# Relay-Board_Rack-PDU_2_1.net
KiCad netlist of a schematic drawn in EAGLE
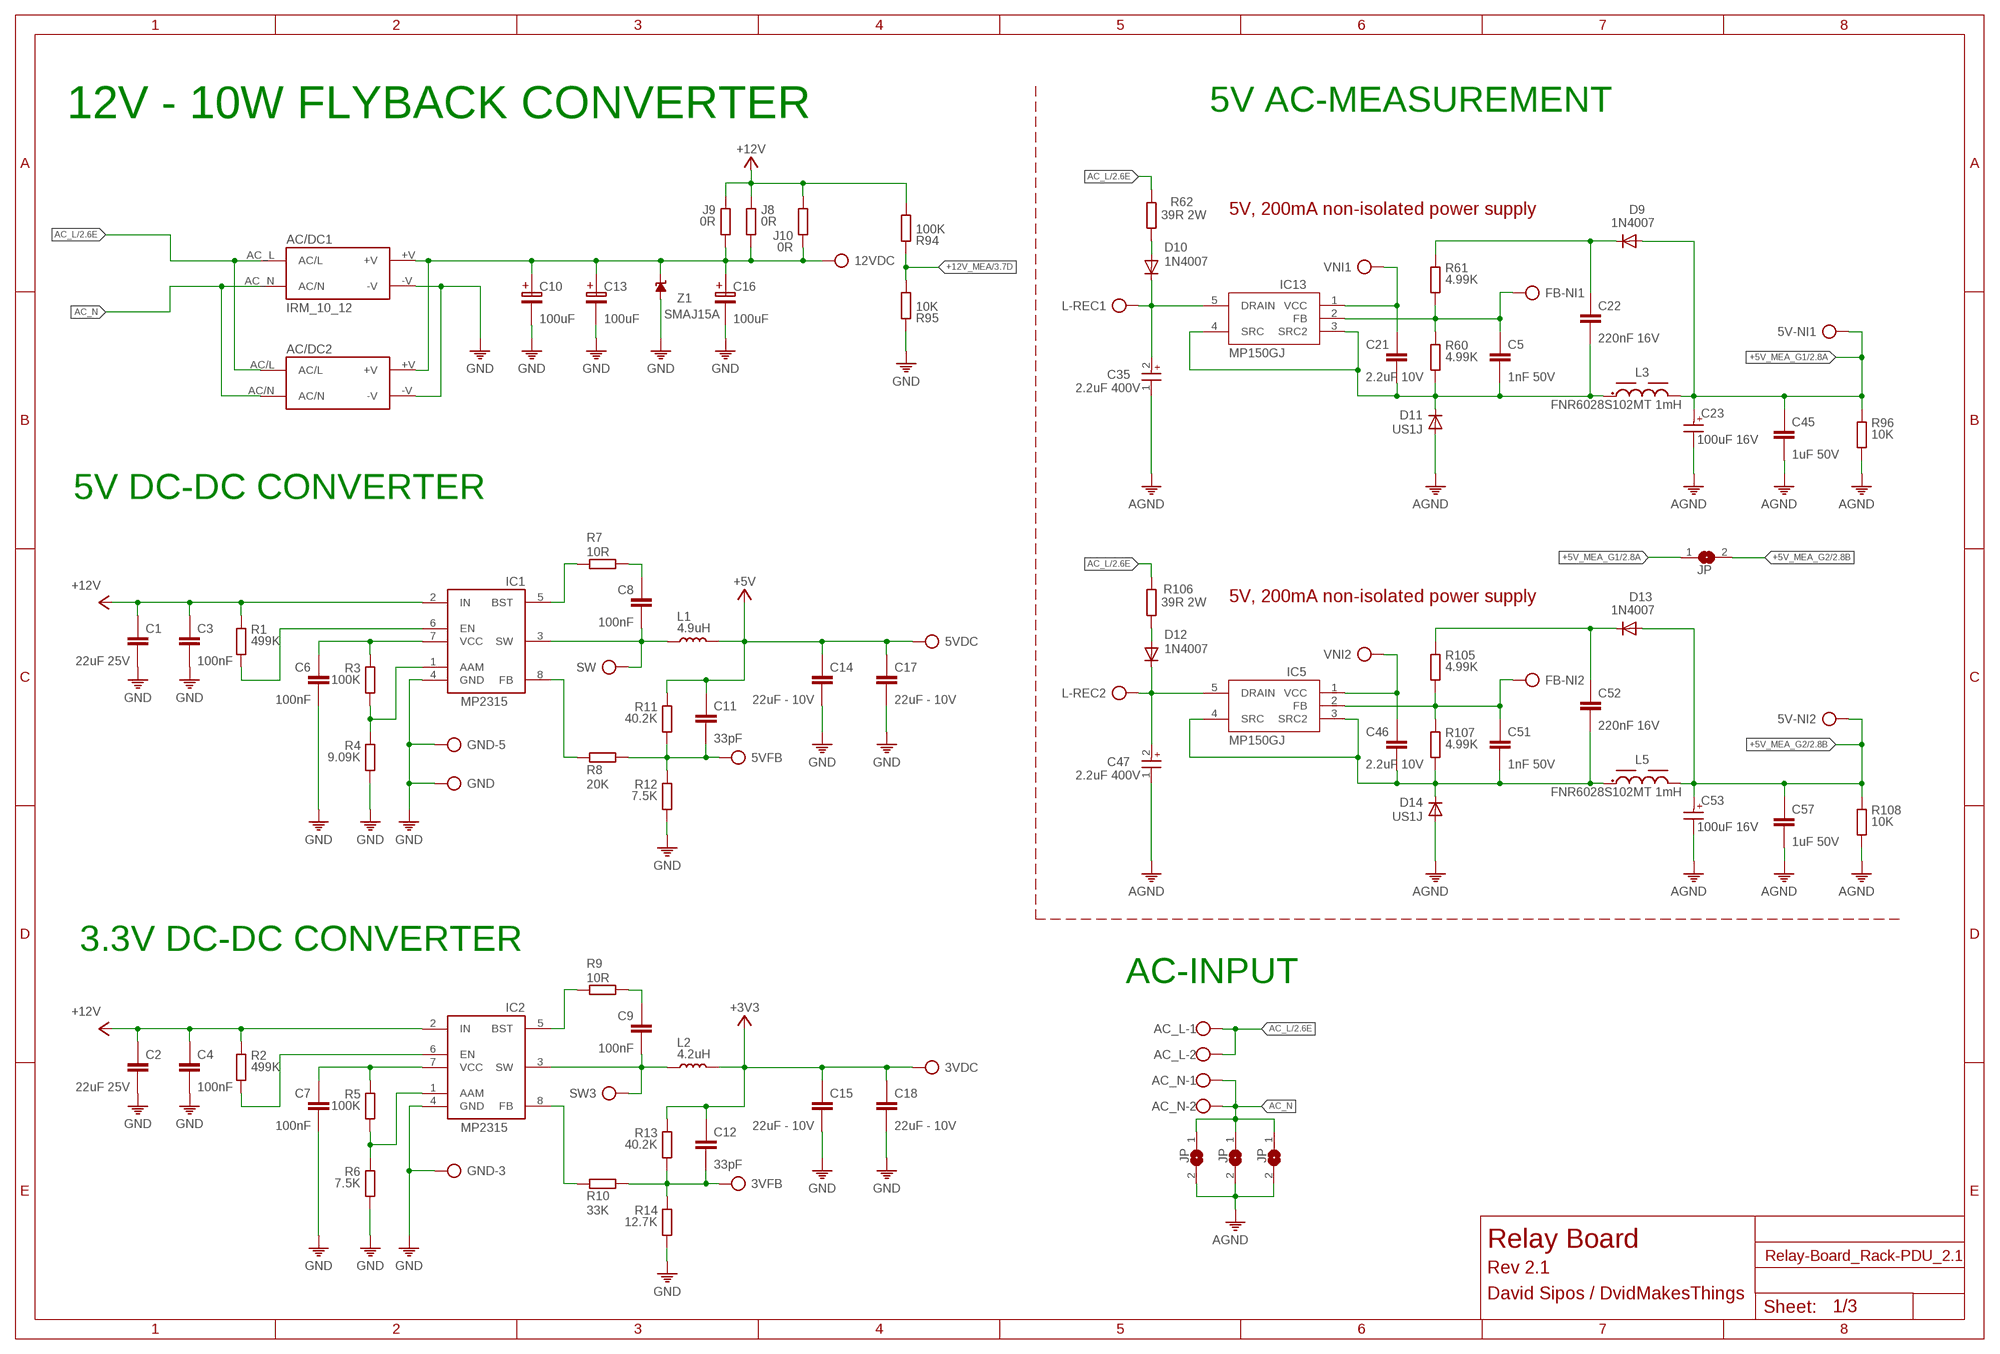
[diagram p0: schematic, sheet 1]
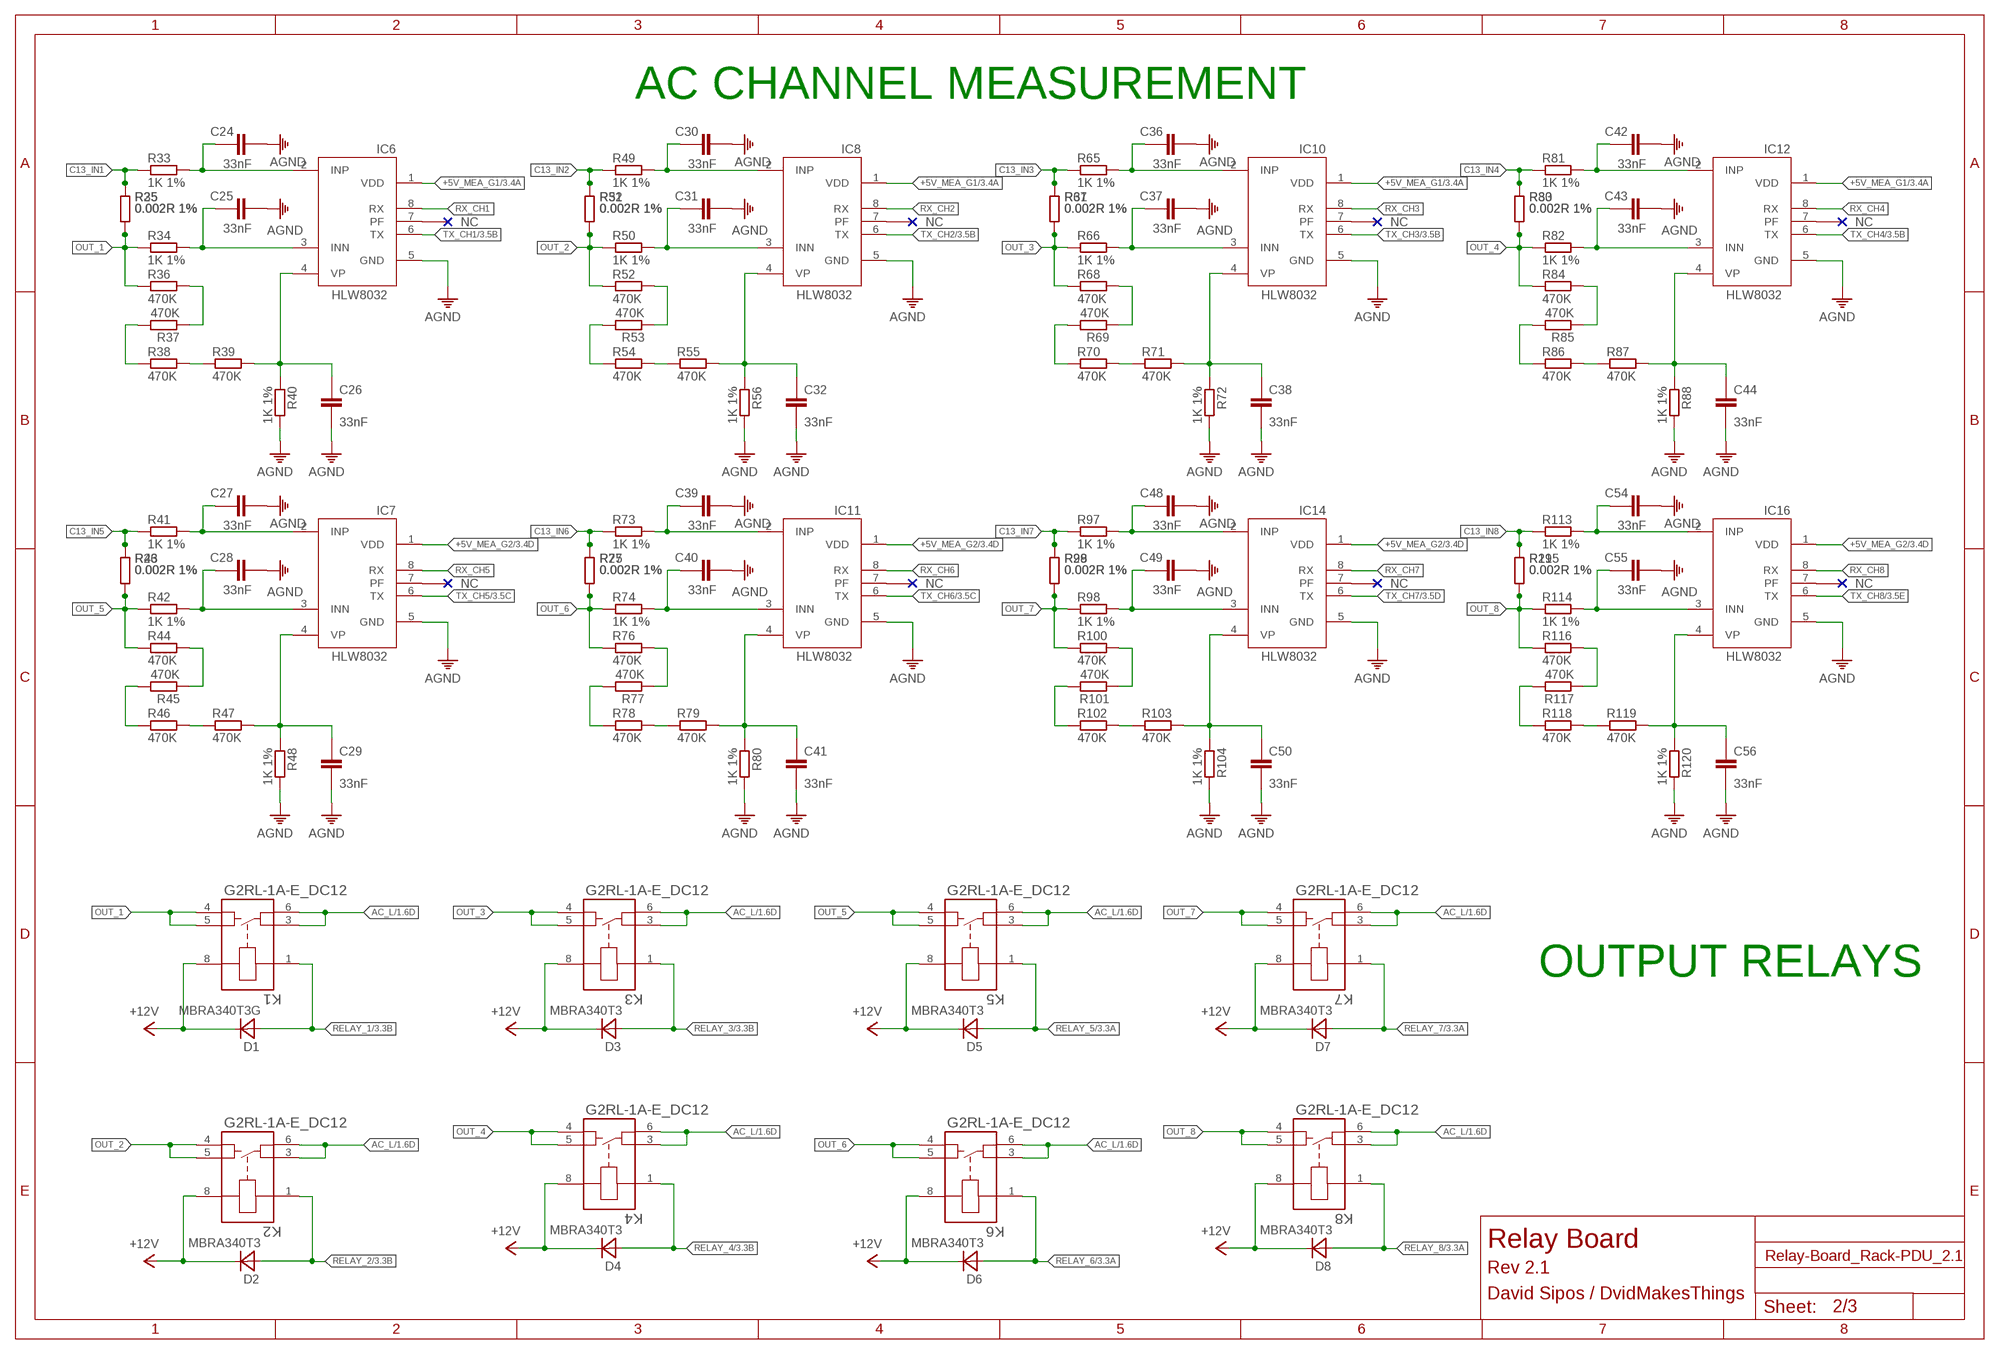
[diagram p1: schematic, sheet 2]
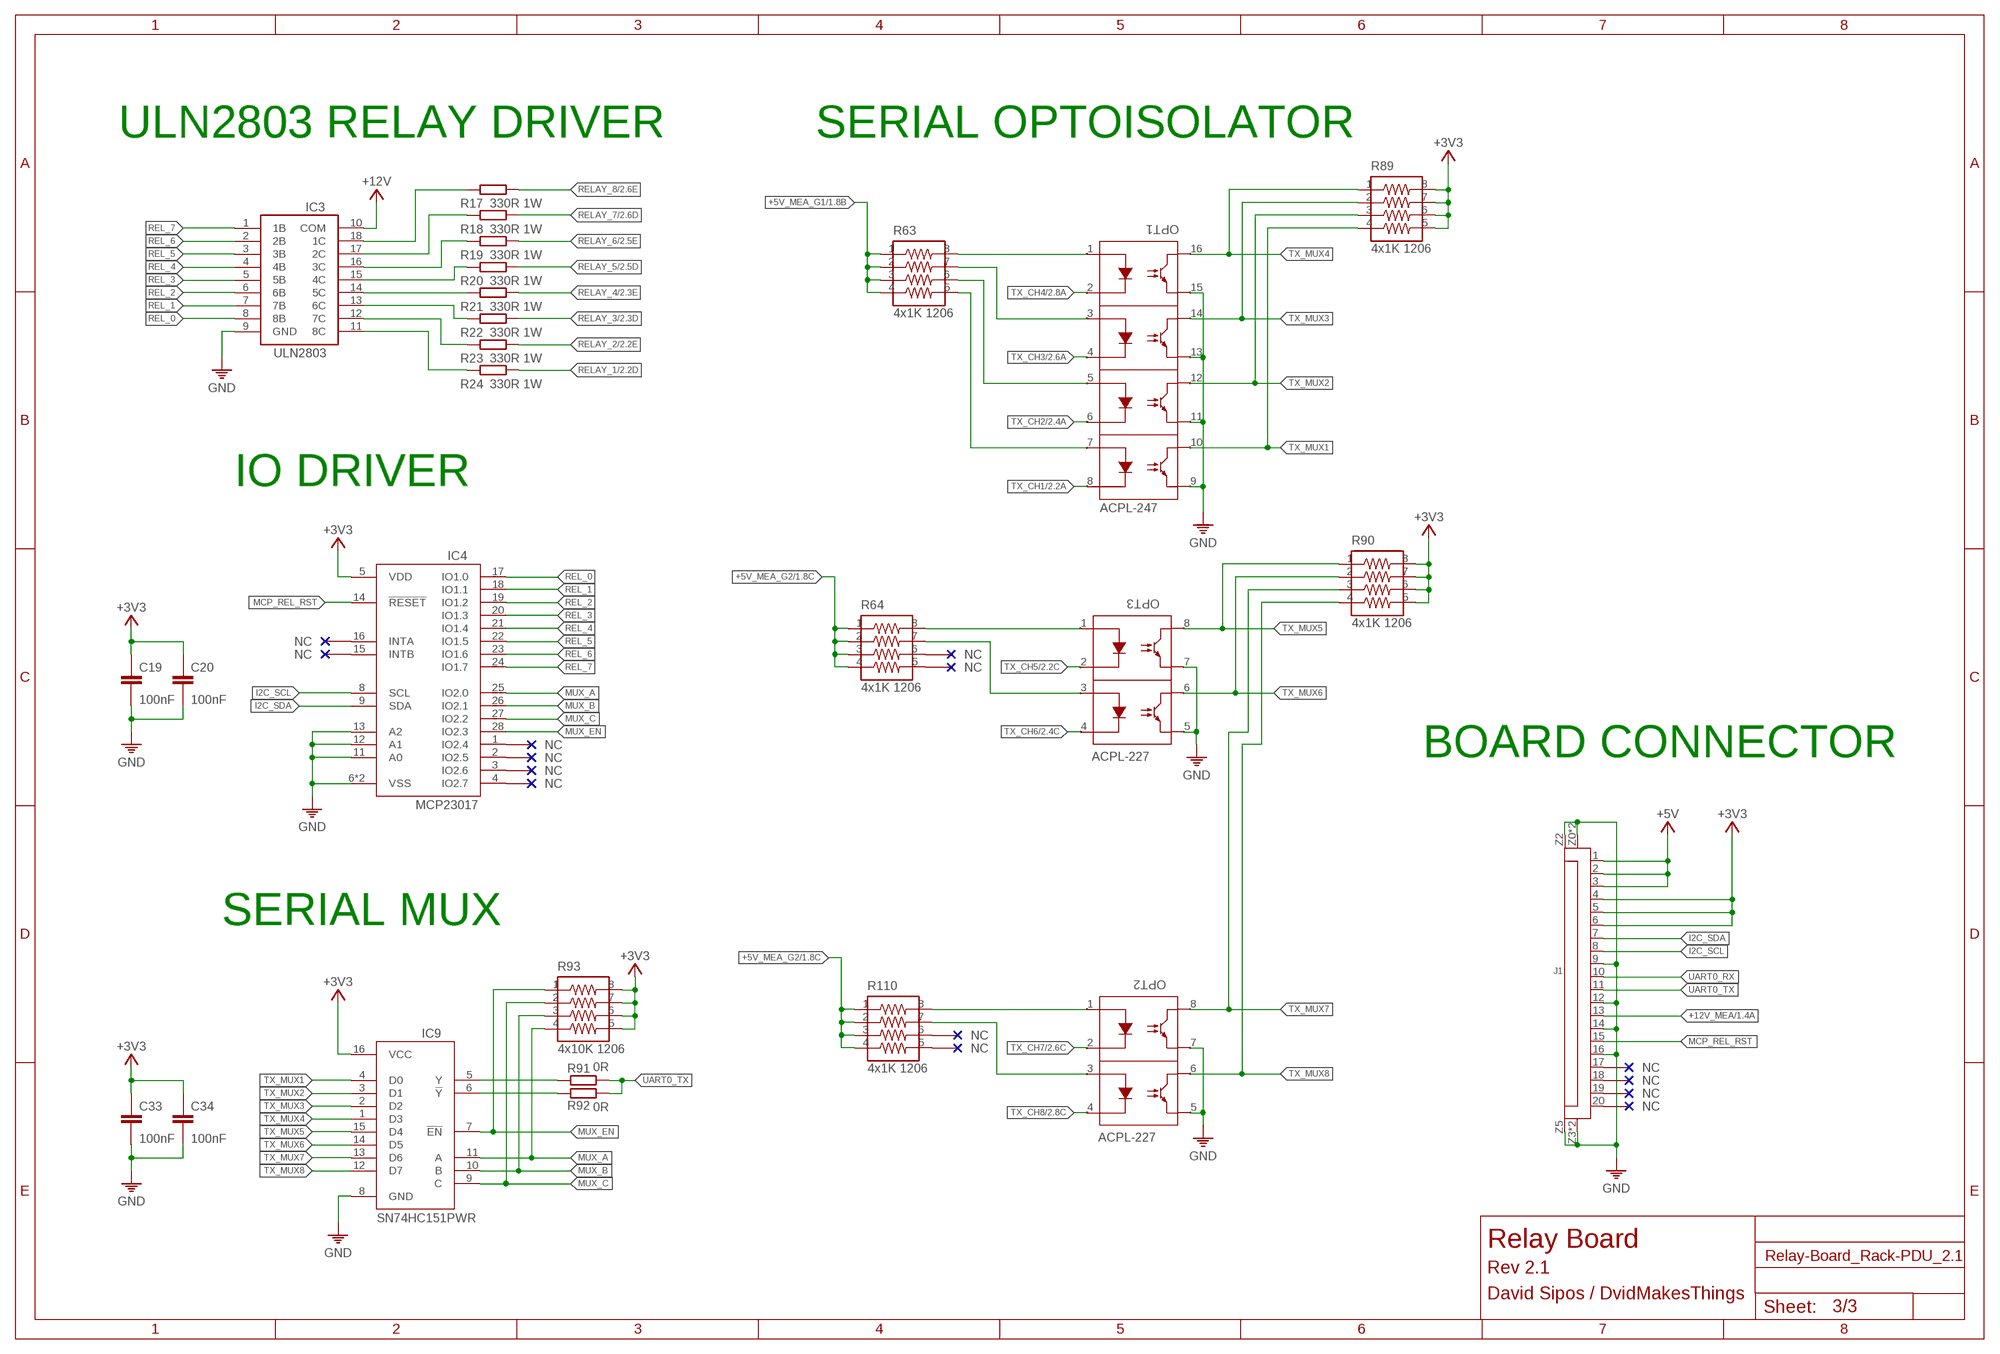
[diagram p2: schematic, sheet 3]

(export (version "E")
  (design (tool "Eeschema 10.0.6"))
  (components
    (comp (ref "C24")
      (value "33nF")
      (footprint "eagle-import:C1206")
      (libsource (lib "eagle-import") (part "C-1206"))
    )
    (comp (ref "C25")
      (value "33nF")
      (footprint "eagle-import:C1206")
      (libsource (lib "eagle-import") (part "C-1206"))
    )
    (comp (ref "C26")
      (value "33nF")
      (footprint "eagle-import:C1206")
      (libsource (lib "eagle-import") (part "C-1206"))
    )
    (comp (ref "C27")
      (value "33nF")
      (footprint "eagle-import:C1206")
      (libsource (lib "eagle-import") (part "C-1206"))
    )
    (comp (ref "C28")
      (value "33nF")
      (footprint "eagle-import:C1206")
      (libsource (lib "eagle-import") (part "C-1206"))
    )
    (comp (ref "C29")
      (value "33nF")
      (footprint "eagle-import:C1206")
      (libsource (lib "eagle-import") (part "C-1206"))
    )
    (comp (ref "C30")
      (value "33nF")
      (footprint "eagle-import:C1206")
      (libsource (lib "eagle-import") (part "C-1206"))
    )
    (comp (ref "C31")
      (value "33nF")
      (footprint "eagle-import:C1206")
      (libsource (lib "eagle-import") (part "C-1206"))
    )
    (comp (ref "C32")
      (value "33nF")
      (footprint "eagle-import:C1206")
      (libsource (lib "eagle-import") (part "C-1206"))
    )
    (comp (ref "C36")
      (value "33nF")
      (footprint "eagle-import:C1206")
      (libsource (lib "eagle-import") (part "C-1206"))
    )
    (comp (ref "C37")
      (value "33nF")
      (footprint "eagle-import:C1206")
      (libsource (lib "eagle-import") (part "C-1206"))
    )
    (comp (ref "C38")
      (value "33nF")
      (footprint "eagle-import:C1206")
      (libsource (lib "eagle-import") (part "C-1206"))
    )
    (comp (ref "C39")
      (value "33nF")
      (footprint "eagle-import:C1206")
      (libsource (lib "eagle-import") (part "C-1206"))
    )
    (comp (ref "C40")
      (value "33nF")
      (footprint "eagle-import:C1206")
      (libsource (lib "eagle-import") (part "C-1206"))
    )
    (comp (ref "C41")
      (value "33nF")
      (footprint "eagle-import:C1206")
      (libsource (lib "eagle-import") (part "C-1206"))
    )
    (comp (ref "C42")
      (value "33nF")
      (footprint "eagle-import:C1206")
      (libsource (lib "eagle-import") (part "C-1206"))
    )
    (comp (ref "C43")
      (value "33nF")
      (footprint "eagle-import:C1206")
      (libsource (lib "eagle-import") (part "C-1206"))
    )
    (comp (ref "C44")
      (value "33nF")
      (footprint "eagle-import:C1206")
      (libsource (lib "eagle-import") (part "C-1206"))
    )
    (comp (ref "C48")
      (value "33nF")
      (footprint "eagle-import:C1206")
      (libsource (lib "eagle-import") (part "C-1206"))
    )
    (comp (ref "C49")
      (value "33nF")
      (footprint "eagle-import:C1206")
      (libsource (lib "eagle-import") (part "C-1206"))
    )
    (comp (ref "C50")
      (value "33nF")
      (footprint "eagle-import:C1206")
      (libsource (lib "eagle-import") (part "C-1206"))
    )
    (comp (ref "C54")
      (value "33nF")
      (footprint "eagle-import:C1206")
      (libsource (lib "eagle-import") (part "C-1206"))
    )
    (comp (ref "C55")
      (value "33nF")
      (footprint "eagle-import:C1206")
      (libsource (lib "eagle-import") (part "C-1206"))
    )
    (comp (ref "C56")
      (value "33nF")
      (footprint "eagle-import:C1206")
      (libsource (lib "eagle-import") (part "C-1206"))
    )
    (comp (ref "D1")
      (value "MBRA340T3G")
      (footprint "eagle-import:SMA")
      (libsource (lib "eagle-import") (part "MBRA340T3"))
    )
    (comp (ref "D2")
      (value "MBRA340T3")
      (footprint "eagle-import:SMA")
      (libsource (lib "eagle-import") (part "MBRA340T3"))
    )
    (comp (ref "D3")
      (value "MBRA340T3")
      (footprint "eagle-import:SMA")
      (libsource (lib "eagle-import") (part "MBRA340T3"))
    )
    (comp (ref "D4")
      (value "MBRA340T3")
      (footprint "eagle-import:SMA")
      (libsource (lib "eagle-import") (part "MBRA340T3"))
    )
    (comp (ref "D5")
      (value "MBRA340T3")
      (footprint "eagle-import:SMA")
      (libsource (lib "eagle-import") (part "MBRA340T3"))
    )
    (comp (ref "D6")
      (value "MBRA340T3")
      (footprint "eagle-import:SMA")
      (libsource (lib "eagle-import") (part "MBRA340T3"))
    )
    (comp (ref "D7")
      (value "MBRA340T3")
      (footprint "eagle-import:SMA")
      (libsource (lib "eagle-import") (part "MBRA340T3"))
    )
    (comp (ref "D8")
      (value "MBRA340T3")
      (footprint "eagle-import:SMA")
      (libsource (lib "eagle-import") (part "MBRA340T3"))
    )
    (comp (ref "IC6")
      (value "HLW8032")
      (footprint "eagle-import:SO8")
      (libsource (lib "eagle-import") (part "HLW8032"))
    )
    (comp (ref "IC7")
      (value "HLW8032")
      (footprint "eagle-import:SO8")
      (libsource (lib "eagle-import") (part "HLW8032"))
    )
    (comp (ref "IC8")
      (value "HLW8032")
      (footprint "eagle-import:SO8")
      (libsource (lib "eagle-import") (part "HLW8032"))
    )
    (comp (ref "IC10")
      (value "HLW8032")
      (footprint "eagle-import:SO8")
      (libsource (lib "eagle-import") (part "HLW8032"))
    )
    (comp (ref "IC11")
      (value "HLW8032")
      (footprint "eagle-import:SO8")
      (libsource (lib "eagle-import") (part "HLW8032"))
    )
    (comp (ref "IC12")
      (value "HLW8032")
      (footprint "eagle-import:SO8")
      (libsource (lib "eagle-import") (part "HLW8032"))
    )
    (comp (ref "IC14")
      (value "HLW8032")
      (footprint "eagle-import:SO8")
      (libsource (lib "eagle-import") (part "HLW8032"))
    )
    (comp (ref "IC16")
      (value "HLW8032")
      (footprint "eagle-import:SO8")
      (libsource (lib "eagle-import") (part "HLW8032"))
    )
    (comp (ref "K1")
      (value "G2RL-1A-E_DC12")
      (footprint "eagle-import:RELAY_G2RL-1A-E_DC5_OMR")
      (fields
        (field (name "MANUFACTURER_PART_NUMBER") "G2RL-1A-E DC12")
        (field (name "COPYRIGHT") "Copyright (C) 2025 Ultra Librarian. All rights reserved.")
      )
      (libsource (lib "eagle-import") (part "G2RL-1A-E_DC12"))
    )
    (comp (ref "K2")
      (value "G2RL-1A-E_DC12")
      (footprint "eagle-import:RELAY_G2RL-1A-E_DC5_OMR")
      (fields
        (field (name "MANUFACTURER_PART_NUMBER") "G2RL-1A-E DC12")
        (field (name "COPYRIGHT") "Copyright (C) 2025 Ultra Librarian. All rights reserved.")
      )
      (libsource (lib "eagle-import") (part "G2RL-1A-E_DC12"))
    )
    (comp (ref "K3")
      (value "G2RL-1A-E_DC12")
      (footprint "eagle-import:RELAY_G2RL-1A-E_DC5_OMR")
      (fields
        (field (name "MANUFACTURER_PART_NUMBER") "G2RL-1A-E DC12")
        (field (name "COPYRIGHT") "Copyright (C) 2025 Ultra Librarian. All rights reserved.")
      )
      (libsource (lib "eagle-import") (part "G2RL-1A-E_DC12"))
    )
    (comp (ref "K4")
      (value "G2RL-1A-E_DC12")
      (footprint "eagle-import:RELAY_G2RL-1A-E_DC5_OMR")
      (fields
        (field (name "MANUFACTURER_PART_NUMBER") "G2RL-1A-E DC12")
        (field (name "COPYRIGHT") "Copyright (C) 2025 Ultra Librarian. All rights reserved.")
      )
      (libsource (lib "eagle-import") (part "G2RL-1A-E_DC12"))
    )
    (comp (ref "K5")
      (value "G2RL-1A-E_DC12")
      (footprint "eagle-import:RELAY_G2RL-1A-E_DC5_OMR")
      (fields
        (field (name "MANUFACTURER_PART_NUMBER") "G2RL-1A-E DC12")
        (field (name "COPYRIGHT") "Copyright (C) 2025 Ultra Librarian. All rights reserved.")
      )
      (libsource (lib "eagle-import") (part "G2RL-1A-E_DC12"))
    )
    (comp (ref "K6")
      (value "G2RL-1A-E_DC12")
      (footprint "eagle-import:RELAY_G2RL-1A-E_DC5_OMR")
      (fields
        (field (name "MANUFACTURER_PART_NUMBER") "G2RL-1A-E DC12")
        (field (name "COPYRIGHT") "Copyright (C) 2025 Ultra Librarian. All rights reserved.")
      )
      (libsource (lib "eagle-import") (part "G2RL-1A-E_DC12"))
    )
    (comp (ref "K7")
      (value "G2RL-1A-E_DC12")
      (footprint "eagle-import:RELAY_G2RL-1A-E_DC5_OMR")
      (fields
        (field (name "MANUFACTURER_PART_NUMBER") "G2RL-1A-E DC12")
        (field (name "COPYRIGHT") "Copyright (C) 2025 Ultra Librarian. All rights reserved.")
      )
      (libsource (lib "eagle-import") (part "G2RL-1A-E_DC12"))
    )
    (comp (ref "K8")
      (value "G2RL-1A-E_DC12")
      (footprint "eagle-import:RELAY_G2RL-1A-E_DC5_OMR")
      (fields
        (field (name "MANUFACTURER_PART_NUMBER") "G2RL-1A-E DC12")
        (field (name "COPYRIGHT") "Copyright (C) 2025 Ultra Librarian. All rights reserved.")
      )
      (libsource (lib "eagle-import") (part "G2RL-1A-E_DC12"))
    )
    (comp (ref "R25")
      (value "0.002R 1%")
      (footprint "eagle-import:2512")
      (libsource (lib "eagle-import") (part "R2512"))
    )
    (comp (ref "R26")
      (value "0.002R 1%")
      (footprint "eagle-import:2512")
      (libsource (lib "eagle-import") (part "R2512"))
    )
    (comp (ref "R27")
      (value "0.002R 1%")
      (footprint "eagle-import:2512")
      (libsource (lib "eagle-import") (part "R2512"))
    )
    (comp (ref "R28")
      (value "0.002R 1%")
      (footprint "eagle-import:2512")
      (libsource (lib "eagle-import") (part "R2512"))
    )
    (comp (ref "R29")
      (value "0.002R 1%")
      (footprint "eagle-import:2512")
      (libsource (lib "eagle-import") (part "R2512"))
    )
    (comp (ref "R30")
      (value "0.002R 1%")
      (footprint "eagle-import:2512")
      (libsource (lib "eagle-import") (part "R2512"))
    )
    (comp (ref "R31")
      (value "0.002R 1%")
      (footprint "eagle-import:2512")
      (libsource (lib "eagle-import") (part "R2512"))
    )
    (comp (ref "R32")
      (value "0.002R 1%")
      (footprint "eagle-import:2512")
      (libsource (lib "eagle-import") (part "R2512"))
    )
    (comp (ref "R33")
      (value "1K 1%")
      (footprint "eagle-import:1206")
      (libsource (lib "eagle-import") (part "R1206"))
    )
    (comp (ref "R34")
      (value "1K 1%")
      (footprint "eagle-import:1206")
      (libsource (lib "eagle-import") (part "R1206"))
    )
    (comp (ref "R35")
      (value "0.002R 1%")
      (footprint "eagle-import:2512")
      (libsource (lib "eagle-import") (part "R2512"))
    )
    (comp (ref "R36")
      (value "470K")
      (footprint "eagle-import:1206")
      (libsource (lib "eagle-import") (part "R1206"))
    )
    (comp (ref "R37")
      (value "470K")
      (footprint "eagle-import:1206")
      (libsource (lib "eagle-import") (part "R1206"))
    )
    (comp (ref "R38")
      (value "470K")
      (footprint "eagle-import:1206")
      (libsource (lib "eagle-import") (part "R1206"))
    )
    (comp (ref "R39")
      (value "470K")
      (footprint "eagle-import:1206")
      (libsource (lib "eagle-import") (part "R1206"))
    )
    (comp (ref "R40")
      (value "1K 1%")
      (footprint "eagle-import:1206")
      (libsource (lib "eagle-import") (part "R1206"))
    )
    (comp (ref "R41")
      (value "1K 1%")
      (footprint "eagle-import:1206")
      (libsource (lib "eagle-import") (part "R1206"))
    )
    (comp (ref "R42")
      (value "1K 1%")
      (footprint "eagle-import:1206")
      (libsource (lib "eagle-import") (part "R1206"))
    )
    (comp (ref "R43")
      (value "0.002R 1%")
      (footprint "eagle-import:2512")
      (libsource (lib "eagle-import") (part "R2512"))
    )
    (comp (ref "R44")
      (value "470K")
      (footprint "eagle-import:1206")
      (libsource (lib "eagle-import") (part "R1206"))
    )
    (comp (ref "R45")
      (value "470K")
      (footprint "eagle-import:1206")
      (libsource (lib "eagle-import") (part "R1206"))
    )
    (comp (ref "R46")
      (value "470K")
      (footprint "eagle-import:1206")
      (libsource (lib "eagle-import") (part "R1206"))
    )
    (comp (ref "R47")
      (value "470K")
      (footprint "eagle-import:1206")
      (libsource (lib "eagle-import") (part "R1206"))
    )
    (comp (ref "R48")
      (value "1K 1%")
      (footprint "eagle-import:1206")
      (libsource (lib "eagle-import") (part "R1206"))
    )
    (comp (ref "R49")
      (value "1K 1%")
      (footprint "eagle-import:1206")
      (libsource (lib "eagle-import") (part "R1206"))
    )
    (comp (ref "R50")
      (value "1K 1%")
      (footprint "eagle-import:1206")
      (libsource (lib "eagle-import") (part "R1206"))
    )
    (comp (ref "R51")
      (value "0.002R 1%")
      (footprint "eagle-import:2512")
      (libsource (lib "eagle-import") (part "R2512"))
    )
    (comp (ref "R52")
      (value "470K")
      (footprint "eagle-import:1206")
      (libsource (lib "eagle-import") (part "R1206"))
    )
    (comp (ref "R53")
      (value "470K")
      (footprint "eagle-import:1206")
      (libsource (lib "eagle-import") (part "R1206"))
    )
    (comp (ref "R54")
      (value "470K")
      (footprint "eagle-import:1206")
      (libsource (lib "eagle-import") (part "R1206"))
    )
    (comp (ref "R55")
      (value "470K")
      (footprint "eagle-import:1206")
      (libsource (lib "eagle-import") (part "R1206"))
    )
    (comp (ref "R56")
      (value "1K 1%")
      (footprint "eagle-import:1206")
      (libsource (lib "eagle-import") (part "R1206"))
    )
    (comp (ref "R65")
      (value "1K 1%")
      (footprint "eagle-import:1206")
      (libsource (lib "eagle-import") (part "R1206"))
    )
    (comp (ref "R66")
      (value "1K 1%")
      (footprint "eagle-import:1206")
      (libsource (lib "eagle-import") (part "R1206"))
    )
    (comp (ref "R67")
      (value "0.002R 1%")
      (footprint "eagle-import:2512")
      (libsource (lib "eagle-import") (part "R2512"))
    )
    (comp (ref "R68")
      (value "470K")
      (footprint "eagle-import:1206")
      (libsource (lib "eagle-import") (part "R1206"))
    )
    (comp (ref "R69")
      (value "470K")
      (footprint "eagle-import:1206")
      (libsource (lib "eagle-import") (part "R1206"))
    )
    (comp (ref "R70")
      (value "470K")
      (footprint "eagle-import:1206")
      (libsource (lib "eagle-import") (part "R1206"))
    )
    (comp (ref "R71")
      (value "470K")
      (footprint "eagle-import:1206")
      (libsource (lib "eagle-import") (part "R1206"))
    )
    (comp (ref "R72")
      (value "1K 1%")
      (footprint "eagle-import:1206")
      (libsource (lib "eagle-import") (part "R1206"))
    )
    (comp (ref "R73")
      (value "1K 1%")
      (footprint "eagle-import:1206")
      (libsource (lib "eagle-import") (part "R1206"))
    )
    (comp (ref "R74")
      (value "1K 1%")
      (footprint "eagle-import:1206")
      (libsource (lib "eagle-import") (part "R1206"))
    )
    (comp (ref "R75")
      (value "0.002R 1%")
      (footprint "eagle-import:2512")
      (libsource (lib "eagle-import") (part "R2512"))
    )
    (comp (ref "R76")
      (value "470K")
      (footprint "eagle-import:1206")
      (libsource (lib "eagle-import") (part "R1206"))
    )
    (comp (ref "R77")
      (value "470K")
      (footprint "eagle-import:1206")
      (libsource (lib "eagle-import") (part "R1206"))
    )
    (comp (ref "R78")
      (value "470K")
      (footprint "eagle-import:1206")
      (libsource (lib "eagle-import") (part "R1206"))
    )
    (comp (ref "R79")
      (value "470K")
      (footprint "eagle-import:1206")
      (libsource (lib "eagle-import") (part "R1206"))
    )
    (comp (ref "R80")
      (value "1K 1%")
      (footprint "eagle-import:1206")
      (libsource (lib "eagle-import") (part "R1206"))
    )
    (comp (ref "R81")
      (value "1K 1%")
      (footprint "eagle-import:1206")
      (libsource (lib "eagle-import") (part "R1206"))
    )
    (comp (ref "R82")
      (value "1K 1%")
      (footprint "eagle-import:1206")
      (libsource (lib "eagle-import") (part "R1206"))
    )
    (comp (ref "R83")
      (value "0.002R 1%")
      (footprint "eagle-import:2512")
      (libsource (lib "eagle-import") (part "R2512"))
    )
    (comp (ref "R84")
      (value "470K")
      (footprint "eagle-import:1206")
      (libsource (lib "eagle-import") (part "R1206"))
    )
    (comp (ref "R85")
      (value "470K")
      (footprint "eagle-import:1206")
      (libsource (lib "eagle-import") (part "R1206"))
    )
    (comp (ref "R86")
      (value "470K")
      (footprint "eagle-import:1206")
      (libsource (lib "eagle-import") (part "R1206"))
    )
    (comp (ref "R87")
      (value "470K")
      (footprint "eagle-import:1206")
      (libsource (lib "eagle-import") (part "R1206"))
    )
    (comp (ref "R88")
      (value "1K 1%")
      (footprint "eagle-import:1206")
      (libsource (lib "eagle-import") (part "R1206"))
    )
    (comp (ref "R97")
      (value "1K 1%")
      (footprint "eagle-import:1206")
      (libsource (lib "eagle-import") (part "R1206"))
    )
    (comp (ref "R98")
      (value "1K 1%")
      (footprint "eagle-import:1206")
      (libsource (lib "eagle-import") (part "R1206"))
    )
    (comp (ref "R99")
      (value "0.002R 1%")
      (footprint "eagle-import:2512")
      (libsource (lib "eagle-import") (part "R2512"))
    )
    (comp (ref "R100")
      (value "470K")
      (footprint "eagle-import:1206")
      (libsource (lib "eagle-import") (part "R1206"))
    )
    (comp (ref "R101")
      (value "470K")
      (footprint "eagle-import:1206")
      (libsource (lib "eagle-import") (part "R1206"))
    )
    (comp (ref "R102")
      (value "470K")
      (footprint "eagle-import:1206")
      (libsource (lib "eagle-import") (part "R1206"))
    )
    (comp (ref "R103")
      (value "470K")
      (footprint "eagle-import:1206")
      (libsource (lib "eagle-import") (part "R1206"))
    )
    (comp (ref "R104")
      (value "1K 1%")
      (footprint "eagle-import:1206")
      (libsource (lib "eagle-import") (part "R1206"))
    )
    (comp (ref "R113")
      (value "1K 1%")
      (footprint "eagle-import:1206")
      (libsource (lib "eagle-import") (part "R1206"))
    )
    (comp (ref "R114")
      (value "1K 1%")
      (footprint "eagle-import:1206")
      (libsource (lib "eagle-import") (part "R1206"))
    )
    (comp (ref "R115")
      (value "0.002R 1%")
      (footprint "eagle-import:2512")
      (libsource (lib "eagle-import") (part "R2512"))
    )
    (comp (ref "R116")
      (value "470K")
      (footprint "eagle-import:1206")
      (libsource (lib "eagle-import") (part "R1206"))
    )
    (comp (ref "R117")
      (value "470K")
      (footprint "eagle-import:1206")
      (libsource (lib "eagle-import") (part "R1206"))
    )
    (comp (ref "R118")
      (value "470K")
      (footprint "eagle-import:1206")
      (libsource (lib "eagle-import") (part "R1206"))
    )
    (comp (ref "R119")
      (value "470K")
      (footprint "eagle-import:1206")
      (libsource (lib "eagle-import") (part "R1206"))
    )
    (comp (ref "R120")
      (value "1K 1%")
      (footprint "eagle-import:1206")
      (libsource (lib "eagle-import") (part "R1206"))
    )
    (comp (ref "C19")
      (value "100nF")
      (footprint "eagle-import:C0402")
      (libsource (lib "eagle-import") (part "C-0402"))
    )
    (comp (ref "C20")
      (value "100nF")
      (footprint "eagle-import:C0402")
      (libsource (lib "eagle-import") (part "C-0402"))
    )
    (comp (ref "C33")
      (value "100nF")
      (footprint "eagle-import:C0402")
      (libsource (lib "eagle-import") (part "C-0402"))
    )
    (comp (ref "C34")
      (value "100nF")
      (footprint "eagle-import:C0402")
      (libsource (lib "eagle-import") (part "C-0402"))
    )
    (comp (ref "IC3")
      (value "ULN2803A")
      (footprint "eagle-import:SO18")
      (libsource (lib "eagle-import") (part "ULN2803"))
    )
    (comp (ref "IC4")
      (value "MCP23017-E/ML")
      (footprint "eagle-import:QFN28[6X6]ML")
      (libsource (lib "eagle-import") (part "MCP23017-E/ML"))
    )
    (comp (ref "IC9")
      (value "SN74HC151PWR")
      (footprint "eagle-import:TSSOP16")
      (libsource (lib "eagle-import") (part "SN74HC151PWR"))
    )
    (comp (ref "J1")
      (value "FPC20-H")
      (footprint "eagle-import:FPC20")
      (libsource (lib "eagle-import") (part "FPC20-H"))
    )
    (comp (ref "OPT1")
      (value "ACPL-247")
      (footprint "eagle-import:SO16")
      (libsource (lib "eagle-import") (part "ACPL-2471"))
    )
    (comp (ref "OPT2")
      (value "ACPL-227")
      (footprint "eagle-import:SO8")
      (libsource (lib "eagle-import") (part "ACPL-227"))
    )
    (comp (ref "OPT3")
      (value "ACPL-227")
      (footprint "eagle-import:SO8")
      (libsource (lib "eagle-import") (part "ACPL-227"))
    )
    (comp (ref "R17")
      (value "330R 1W")
      (footprint "eagle-import:2512")
      (libsource (lib "eagle-import") (part "R2512"))
    )
    (comp (ref "R18")
      (value "330R 1W")
      (footprint "eagle-import:2512")
      (libsource (lib "eagle-import") (part "R2512"))
    )
    (comp (ref "R19")
      (value "330R 1W")
      (footprint "eagle-import:2512")
      (libsource (lib "eagle-import") (part "R2512"))
    )
    (comp (ref "R20")
      (value "330R 1W")
      (footprint "eagle-import:2512")
      (libsource (lib "eagle-import") (part "R2512"))
    )
    (comp (ref "R21")
      (value "330R 1W")
      (footprint "eagle-import:2512")
      (libsource (lib "eagle-import") (part "R2512"))
    )
    (comp (ref "R22")
      (value "330R 1W")
      (footprint "eagle-import:2512")
      (libsource (lib "eagle-import") (part "R2512"))
    )
    (comp (ref "R23")
      (value "330R 1W")
      (footprint "eagle-import:2512")
      (libsource (lib "eagle-import") (part "R2512"))
    )
    (comp (ref "R24")
      (value "330R 1W")
      (footprint "eagle-import:2512")
      (libsource (lib "eagle-import") (part "R2512"))
    )
    (comp (ref "R63")
      (value "4x1K 1206")
      (footprint "eagle-import:742C083103JP")
      (fields
        (field (name "MANUFACTURER") "CTS Resistor Products")
        (field (name "MPN") "742C083103JP")
        (field (name "CREATED_BY") "PCBLayout.com")
      )
      (libsource (lib "eagle-import") (part "742C083103JP"))
    )
    (comp (ref "R64")
      (value "4x1K 1206")
      (footprint "eagle-import:742C083103JP")
      (fields
        (field (name "MANUFACTURER") "CTS Resistor Products")
        (field (name "MPN") "742C083103JP")
        (field (name "CREATED_BY") "PCBLayout.com")
      )
      (libsource (lib "eagle-import") (part "742C083103JP"))
    )
    (comp (ref "R89")
      (value "4x1K 1206")
      (footprint "eagle-import:742C083103JP")
      (fields
        (field (name "MANUFACTURER") "CTS Resistor Products")
        (field (name "MPN") "742C083103JP")
        (field (name "CREATED_BY") "PCBLayout.com")
      )
      (libsource (lib "eagle-import") (part "742C083103JP"))
    )
    (comp (ref "R90")
      (value "4x1K 1206")
      (footprint "eagle-import:742C083103JP")
      (fields
        (field (name "MANUFACTURER") "CTS Resistor Products")
        (field (name "MPN") "742C083103JP")
        (field (name "CREATED_BY") "PCBLayout.com")
      )
      (libsource (lib "eagle-import") (part "742C083103JP"))
    )
    (comp (ref "R91")
      (value "0R")
      (footprint "eagle-import:0402")
      (libsource (lib "eagle-import") (part "R0402"))
    )
    (comp (ref "R92")
      (value "0R")
      (footprint "eagle-import:0402")
      (libsource (lib "eagle-import") (part "R0402"))
    )
    (comp (ref "R93")
      (value "4x10K 1206")
      (footprint "eagle-import:742C083103JP")
      (fields
        (field (name "MANUFACTURER") "CTS Resistor Products")
        (field (name "MPN") "742C083103JP")
        (field (name "CREATED_BY") "PCBLayout.com")
      )
      (libsource (lib "eagle-import") (part "742C083103JP"))
    )
    (comp (ref "R110")
      (value "4x1K 1206")
      (footprint "eagle-import:742C083103JP")
      (fields
        (field (name "MANUFACTURER") "CTS Resistor Products")
        (field (name "MPN") "742C083103JP")
        (field (name "CREATED_BY") "PCBLayout.com")
      )
      (libsource (lib "eagle-import") (part "742C083103JP"))
    )
    (comp (ref "3VDC")
      (value "TP")
      (footprint "eagle-import:TP")
      (libsource (lib "eagle-import") (part "TP"))
    )
    (comp (ref "3VFB")
      (value "TP")
      (footprint "eagle-import:TP")
      (libsource (lib "eagle-import") (part "TP"))
    )
    (comp (ref "5V-NI1")
      (value "TP")
      (footprint "eagle-import:TP")
      (libsource (lib "eagle-import") (part "TP"))
    )
    (comp (ref "5V-NI2")
      (value "TP")
      (footprint "eagle-import:TP")
      (libsource (lib "eagle-import") (part "TP"))
    )
    (comp (ref "5VDC")
      (value "TP")
      (footprint "eagle-import:TP")
      (libsource (lib "eagle-import") (part "TP"))
    )
    (comp (ref "5VFB")
      (value "TP")
      (footprint "eagle-import:TP")
      (libsource (lib "eagle-import") (part "TP"))
    )
    (comp (ref "12VDC")
      (value "TP")
      (footprint "eagle-import:TP")
      (libsource (lib "eagle-import") (part "TP"))
    )
    (comp (ref "AC/DC1")
      (value "IRM_10_12")
      (footprint "eagle-import:IRM_10_12")
      (libsource (lib "eagle-import") (part "IRM_10_12"))
    )
    (comp (ref "AC/DC2")
      (value "IRM_10_12-2")
      (footprint "eagle-import:IRM_15_12")
      (libsource (lib "eagle-import") (part "IRM_10_12-2"))
    )
    (comp (ref "AC_L")
      (value "W237-102")
      (footprint "eagle-import:W237-102")
      (fields (field (name "MPN") "237-102"))
      (libsource (lib "eagle-import") (part "W237-102"))
    )
    (comp (ref "AC_N")
      (value "W237-102")
      (footprint "eagle-import:W237-102")
      (fields (field (name "MPN") "237-102"))
      (libsource (lib "eagle-import") (part "W237-102"))
    )
    (comp (ref "C1")
      (value "22uF 25V")
      (footprint "eagle-import:C1206")
      (libsource (lib "eagle-import") (part "C-1206"))
    )
    (comp (ref "C2")
      (value "22uF 25V")
      (footprint "eagle-import:C1206")
      (libsource (lib "eagle-import") (part "C-1206"))
    )
    (comp (ref "C3")
      (value "100nF")
      (footprint "eagle-import:0402")
      (libsource (lib "eagle-import") (part "C0402"))
    )
    (comp (ref "C4")
      (value "100nF")
      (footprint "eagle-import:0402")
      (libsource (lib "eagle-import") (part "C0402"))
    )
    (comp (ref "C5")
      (value "1nF 50V")
      (footprint "eagle-import:C0603")
      (libsource (lib "eagle-import") (part "C-0603"))
    )
    (comp (ref "C6")
      (value "100nF")
      (footprint "eagle-import:0402")
      (libsource (lib "eagle-import") (part "C0402"))
    )
    (comp (ref "C7")
      (value "100nF")
      (footprint "eagle-import:0402")
      (libsource (lib "eagle-import") (part "C0402"))
    )
    (comp (ref "C8")
      (value "100nF")
      (footprint "eagle-import:0402")
      (libsource (lib "eagle-import") (part "C0402"))
    )
    (comp (ref "C9")
      (value "100nF")
      (footprint "eagle-import:0402")
      (libsource (lib "eagle-import") (part "C0402"))
    )
    (comp (ref "C10")
      (value "100uF")
      (footprint "eagle-import:100UF-16V")
      (libsource (lib "eagle-import") (part "CPOL"))
    )
    (comp (ref "C11")
      (value "33pF")
      (footprint "eagle-import:0402")
      (libsource (lib "eagle-import") (part "C0402"))
    )
    (comp (ref "C12")
      (value "33pF")
      (footprint "eagle-import:0402")
      (libsource (lib "eagle-import") (part "C0402"))
    )
    (comp (ref "C13")
      (value "100uF")
      (footprint "eagle-import:100UF-16V")
      (libsource (lib "eagle-import") (part "CPOL"))
    )
    (comp (ref "C14")
      (value "22uF - 10V")
      (footprint "eagle-import:C1206")
      (libsource (lib "eagle-import") (part "C-1206"))
    )
    (comp (ref "C15")
      (value "22uF - 10V")
      (footprint "eagle-import:C1206")
      (libsource (lib "eagle-import") (part "C-1206"))
    )
    (comp (ref "C16")
      (value "100uF")
      (footprint "eagle-import:100UF-16V")
      (libsource (lib "eagle-import") (part "CPOL"))
    )
    (comp (ref "C17")
      (value "22uF - 10V")
      (footprint "eagle-import:C1206")
      (libsource (lib "eagle-import") (part "C-1206"))
    )
    (comp (ref "C18")
      (value "22uF - 10V")
      (footprint "eagle-import:C1206")
      (libsource (lib "eagle-import") (part "C-1206"))
    )
    (comp (ref "C21")
      (value "2.2uF 10V")
      (footprint "eagle-import:C0603")
      (libsource (lib "eagle-import") (part "C-0603"))
    )
    (comp (ref "C22")
      (value "220nF 16V")
      (footprint "eagle-import:C0805")
      (libsource (lib "eagle-import") (part "C-0805"))
    )
    (comp (ref "C23")
      (value "100uF 16V")
      (footprint "eagle-import:WCAP-PSHP_6.3X5.8(DXL)")
      (libsource (lib "eagle-import") (part "WCAP-PSHP_6.3X5.8_875115644009"))
    )
    (comp (ref "C35")
      (value "2.2uF 400V")
      (footprint "eagle-import:WCAP-HSAH_D6.3H7.7P2.2")
      (libsource (lib "eagle-import") (part "WCAP-HSAH_D6.3H7.7P2.2_875585745003"))
    )
    (comp (ref "C45")
      (value "1uF 50V")
      (footprint "eagle-import:C0805")
      (libsource (lib "eagle-import") (part "C-0805"))
    )
    (comp (ref "C46")
      (value "2.2uF 10V")
      (footprint "eagle-import:C0603")
      (libsource (lib "eagle-import") (part "C-0603"))
    )
    (comp (ref "C47")
      (value "2.2uF 400V")
      (footprint "eagle-import:WCAP-HSAH_D6.3H7.7P2.2")
      (libsource (lib "eagle-import") (part "WCAP-HSAH_D6.3H7.7P2.2_875585745003"))
    )
    (comp (ref "C51")
      (value "1nF 50V")
      (footprint "eagle-import:C0603")
      (libsource (lib "eagle-import") (part "C-0603"))
    )
    (comp (ref "C52")
      (value "220nF 16V")
      (footprint "eagle-import:C0805")
      (libsource (lib "eagle-import") (part "C-0805"))
    )
    (comp (ref "C53")
      (value "100uF 16V")
      (footprint "eagle-import:WCAP-PSHP_6.3X5.8(DXL)")
      (libsource (lib "eagle-import") (part "WCAP-PSHP_6.3X5.8_875115644009"))
    )
    (comp (ref "C57")
      (value "1uF 50V")
      (footprint "eagle-import:C0805")
      (libsource (lib "eagle-import") (part "C-0805"))
    )
    (comp (ref "D9")
      (value "1N4007")
      (footprint "eagle-import:SMA")
      (libsource (lib "eagle-import") (part "S1M"))
    )
    (comp (ref "D10")
      (value "1N4007")
      (footprint "eagle-import:SMA")
      (libsource (lib "eagle-import") (part "S1M"))
    )
    (comp (ref "D11")
      (value "US1J")
      (footprint "eagle-import:SMA")
      (libsource (lib "eagle-import") (part "S1M"))
    )
    (comp (ref "D12")
      (value "1N4007")
      (footprint "eagle-import:SMA")
      (libsource (lib "eagle-import") (part "S1M"))
    )
    (comp (ref "D13")
      (value "1N4007")
      (footprint "eagle-import:SMA")
      (libsource (lib "eagle-import") (part "S1M"))
    )
    (comp (ref "D14")
      (value "US1J")
      (footprint "eagle-import:SMA")
      (libsource (lib "eagle-import") (part "S1M"))
    )
    (comp (ref "FB-NI1")
      (value "TP")
      (footprint "eagle-import:TP")
      (libsource (lib "eagle-import") (part "TP"))
    )
    (comp (ref "FB-NI2")
      (value "TP")
      (footprint "eagle-import:TP")
      (libsource (lib "eagle-import") (part "TP"))
    )
    (comp (ref "GND") (value "TP") (footprint "eagle-import:TP") (libsource (lib "eagle-import") (part "TP")))
    (comp (ref "GND-3")
      (value "TP")
      (footprint "eagle-import:TP")
      (libsource (lib "eagle-import") (part "TP"))
    )
    (comp (ref "GND-5")
      (value "TP")
      (footprint "eagle-import:TP")
      (libsource (lib "eagle-import") (part "TP"))
    )
    (comp (ref "IC1")
      (value "MP2315GJ-Z")
      (footprint "eagle-import:SOT65P280X110-8N")
      (libsource (lib "eagle-import") (part "MP2315TSOT23-8"))
    )
    (comp (ref "IC2")
      (value "MP2315S")
      (footprint "eagle-import:SOT65P280X110-8N")
      (libsource (lib "eagle-import") (part "MP2315TSOT23-8"))
    )
    (comp (ref "IC5")
      (value "MP150GJ")
      (footprint "eagle-import:SOT23-5")
      (libsource (lib "eagle-import") (part "MP150GJ"))
    )
    (comp (ref "IC13")
      (value "MP150GJ")
      (footprint "eagle-import:SOT23-5")
      (libsource (lib "eagle-import") (part "MP150GJ"))
    )
    (comp (ref "J7") (value "JP") (footprint "eagle-import:SJ") (libsource (lib "eagle-import") (part "SJ")))
    (comp (ref "J8")
      (value "0R")
      (footprint "eagle-import:0805")
      (libsource (lib "eagle-import") (part "R0805"))
    )
    (comp (ref "J9")
      (value "0R")
      (footprint "eagle-import:0805")
      (libsource (lib "eagle-import") (part "R0805"))
    )
    (comp (ref "J10")
      (value "0R")
      (footprint "eagle-import:0805")
      (libsource (lib "eagle-import") (part "R0805"))
    )
    (comp (ref "L-REC1")
      (value "TP")
      (footprint "eagle-import:TP")
      (libsource (lib "eagle-import") (part "TP"))
    )
    (comp (ref "L-REC2")
      (value "TP")
      (footprint "eagle-import:TP")
      (libsource (lib "eagle-import") (part "TP"))
    )
    (comp (ref "L1")
      (value "4.9uH")
      (footprint "eagle-import:SRR5228A")
      (libsource (lib "eagle-import") (part "L"))
    )
    (comp (ref "L2")
      (value "4.2uH")
      (footprint "eagle-import:SRR5228A")
      (libsource (lib "eagle-import") (part "L"))
    )
    (comp (ref "L3")
      (value "FNR6028S102MT 1mH")
      (footprint "eagle-import:WE-HEPA_6030")
      (libsource (lib "eagle-import") (part "WE-HEPA_6030_78408063006"))
    )
    (comp (ref "L5")
      (value "FNR6028S102MT 1mH")
      (footprint "eagle-import:WE-HEPA_6030")
      (libsource (lib "eagle-import") (part "WE-HEPA_6030_78408063006"))
    )
    (comp (ref "R1")
      (value "499K")
      (footprint "eagle-import:0402")
      (libsource (lib "eagle-import") (part "R0402"))
    )
    (comp (ref "R2")
      (value "499K")
      (footprint "eagle-import:0402")
      (libsource (lib "eagle-import") (part "R0402"))
    )
    (comp (ref "R3")
      (value "100K")
      (footprint "eagle-import:0402")
      (libsource (lib "eagle-import") (part "R0402"))
    )
    (comp (ref "R4")
      (value "9.09K")
      (footprint "eagle-import:0402")
      (libsource (lib "eagle-import") (part "R0402"))
    )
    (comp (ref "R5")
      (value "100K")
      (footprint "eagle-import:0402")
      (libsource (lib "eagle-import") (part "R0402"))
    )
    (comp (ref "R6")
      (value "7.5K")
      (footprint "eagle-import:0402")
      (libsource (lib "eagle-import") (part "R0402"))
    )
    (comp (ref "R7")
      (value "10R")
      (footprint "eagle-import:0402")
      (libsource (lib "eagle-import") (part "R0402"))
    )
    (comp (ref "R8")
      (value "20K")
      (footprint "eagle-import:0402")
      (libsource (lib "eagle-import") (part "R0402"))
    )
    (comp (ref "R9")
      (value "10R")
      (footprint "eagle-import:0402")
      (libsource (lib "eagle-import") (part "R0402"))
    )
    (comp (ref "R10")
      (value "33K")
      (footprint "eagle-import:0402")
      (libsource (lib "eagle-import") (part "R0402"))
    )
    (comp (ref "R11")
      (value "40.2K")
      (footprint "eagle-import:0402")
      (libsource (lib "eagle-import") (part "R0402"))
    )
    (comp (ref "R12")
      (value "7.5K")
      (footprint "eagle-import:0402")
      (libsource (lib "eagle-import") (part "R0402"))
    )
    (comp (ref "R13")
      (value "40.2K")
      (footprint "eagle-import:0402")
      (libsource (lib "eagle-import") (part "R0402"))
    )
    (comp (ref "R14")
      (value "12.7K")
      (footprint "eagle-import:0402")
      (libsource (lib "eagle-import") (part "R0402"))
    )
    (comp (ref "R57") (value "JP") (footprint "eagle-import:SJ") (libsource (lib "eagle-import") (part "SJ")))
    (comp (ref "R58") (value "JP") (footprint "eagle-import:SJ") (libsource (lib "eagle-import") (part "SJ")))
    (comp (ref "R59") (value "JP") (footprint "eagle-import:SJ") (libsource (lib "eagle-import") (part "SJ")))
    (comp (ref "R60")
      (value "4.99K")
      (footprint "eagle-import:0603")
      (libsource (lib "eagle-import") (part "R0603"))
    )
    (comp (ref "R61")
      (value "4.99K")
      (footprint "eagle-import:0603")
      (libsource (lib "eagle-import") (part "R0603"))
    )
    (comp (ref "R62")
      (value "39R 2W")
      (footprint "eagle-import:2512")
      (libsource (lib "eagle-import") (part "R2512"))
    )
    (comp (ref "R94")
      (value "100K")
      (footprint "eagle-import:0402")
      (libsource (lib "eagle-import") (part "R0402"))
    )
    (comp (ref "R95")
      (value "10K")
      (footprint "eagle-import:0402")
      (libsource (lib "eagle-import") (part "R0402"))
    )
    (comp (ref "R96")
      (value "10K")
      (footprint "eagle-import:0805")
      (libsource (lib "eagle-import") (part "R0805"))
    )
    (comp (ref "R105")
      (value "4.99K")
      (footprint "eagle-import:0603")
      (libsource (lib "eagle-import") (part "R0603"))
    )
    (comp (ref "R106")
      (value "39R 2W")
      (footprint "eagle-import:2512")
      (libsource (lib "eagle-import") (part "R2512"))
    )
    (comp (ref "R107")
      (value "4.99K")
      (footprint "eagle-import:0603")
      (libsource (lib "eagle-import") (part "R0603"))
    )
    (comp (ref "R108")
      (value "10K")
      (footprint "eagle-import:0805")
      (libsource (lib "eagle-import") (part "R0805"))
    )
    (comp (ref "SW") (value "TP") (footprint "eagle-import:TP") (libsource (lib "eagle-import") (part "TP")))
    (comp (ref "SW3") (value "TP") (footprint "eagle-import:TP") (libsource (lib "eagle-import") (part "TP")))
    (comp (ref "VNI1")
      (value "TP")
      (footprint "eagle-import:TP")
      (libsource (lib "eagle-import") (part "TP"))
    )
    (comp (ref "VNI2")
      (value "TP")
      (footprint "eagle-import:TP")
      (libsource (lib "eagle-import") (part "TP"))
    )
    (comp (ref "Z1")
      (value "SMAJ15A")
      (footprint "eagle-import:SUPRESSOR_SMAJ")
      (libsource (lib "eagle-import") (part "SUPRESSOR_TVS-UD-SMAJ"))
    )
  )
  (nets
    (net (code "1") (name "+3V3") (class "Default")
      (node (ref "3VDC") (pin "TP") (pinfunction "P$1_TP") (pintype "bidirectional"))
      (node (ref "C12") (pin "1") (pinfunction "1_1") (pintype "passive"))
      (node (ref "C15") (pin "1") (pinfunction "1_1") (pintype "passive"))
      (node (ref "C18") (pin "1") (pinfunction "1_1") (pintype "passive"))
      (node (ref "C19") (pin "1") (pinfunction "1_1") (pintype "passive"))
      (node (ref "C20") (pin "1") (pinfunction "1_1") (pintype "passive"))
      (node (ref "C33") (pin "1") (pinfunction "1_1") (pintype "passive"))
      (node (ref "C34") (pin "1") (pinfunction "1_1") (pintype "passive"))
      (node (ref "IC4") (pin "5") (pinfunction "VDD_5") (pintype "bidirectional"))
      (node (ref "IC9") (pin "16") (pinfunction "VCC_16") (pintype "power_in"))
      (node (ref "J1") (pin "4") (pinfunction "4_4") (pintype "bidirectional"))
      (node (ref "J1") (pin "5") (pinfunction "5_5") (pintype "bidirectional"))
      (node (ref "J1") (pin "6") (pinfunction "6_6") (pintype "bidirectional"))
      (node (ref "L2") (pin "2") (pinfunction "2_2") (pintype "passive"))
      (node (ref "R13") (pin "1") (pinfunction "1_1") (pintype "passive"))
      (node (ref "R89") (pin "5") (pinfunction "5_5") (pintype "passive"))
      (node (ref "R89") (pin "6") (pinfunction "6_6") (pintype "passive"))
      (node (ref "R89") (pin "7") (pinfunction "7_7") (pintype "passive"))
      (node (ref "R89") (pin "8") (pinfunction "8_8") (pintype "passive"))
      (node (ref "R90") (pin "5") (pinfunction "5_5") (pintype "passive"))
      (node (ref "R90") (pin "6") (pinfunction "6_6") (pintype "passive"))
      (node (ref "R90") (pin "7") (pinfunction "7_7") (pintype "passive"))
      (node (ref "R90") (pin "8") (pinfunction "8_8") (pintype "passive"))
      (node (ref "R93") (pin "5") (pinfunction "5_5") (pintype "passive"))
      (node (ref "R93") (pin "6") (pinfunction "6_6") (pintype "passive"))
      (node (ref "R93") (pin "7") (pinfunction "7_7") (pintype "passive"))
      (node (ref "R93") (pin "8") (pinfunction "8_8") (pintype "passive"))
    )
    (net (code "2") (name "+5V") (class "Default")
      (node (ref "5VDC") (pin "TP") (pinfunction "P$1_TP") (pintype "bidirectional"))
      (node (ref "C11") (pin "1") (pinfunction "1_1") (pintype "passive"))
      (node (ref "C14") (pin "1") (pinfunction "1_1") (pintype "passive"))
      (node (ref "C17") (pin "1") (pinfunction "1_1") (pintype "passive"))
      (node (ref "J1") (pin "1") (pinfunction "1_1") (pintype "bidirectional"))
      (node (ref "J1") (pin "2") (pinfunction "2_2") (pintype "bidirectional"))
      (node (ref "J1") (pin "3") (pinfunction "3_3") (pintype "bidirectional"))
      (node (ref "L1") (pin "2") (pinfunction "2_2") (pintype "passive"))
      (node (ref "R11") (pin "1") (pinfunction "1_1") (pintype "passive"))
    )
    (net (code "3") (name "+5V_MEA_G1") (class "Default")
      (node (ref "5V-NI1") (pin "TP") (pinfunction "P$1_TP") (pintype "bidirectional"))
      (node (ref "C23") (pin "1") (pinfunction "+_1") (pintype "passive"))
      (node (ref "C45") (pin "2") (pinfunction "2_2") (pintype "passive"))
      (node (ref "D9") (pin "A") (pinfunction "A_A") (pintype "passive"))
      (node (ref "IC10") (pin "1") (pinfunction "VDD_1") (pintype "power_in"))
      (node (ref "IC12") (pin "1") (pinfunction "VDD_1") (pintype "power_in"))
      (node (ref "IC6") (pin "1") (pinfunction "VDD_1") (pintype "power_in"))
      (node (ref "IC8") (pin "1") (pinfunction "VDD_1") (pintype "power_in"))
      (node (ref "J7") (pin "1") (pinfunction "1_1") (pintype "passive"))
      (node (ref "L3") (pin "2") (pinfunction "2_2") (pintype "passive"))
      (node (ref "R63") (pin "1") (pinfunction "1_1") (pintype "passive"))
      (node (ref "R63") (pin "2") (pinfunction "2_2") (pintype "passive"))
      (node (ref "R63") (pin "3") (pinfunction "3_3") (pintype "passive"))
      (node (ref "R63") (pin "4") (pinfunction "4_4") (pintype "passive"))
      (node (ref "R96") (pin "1") (pinfunction "1_1") (pintype "passive"))
    )
    (net (code "4") (name "+5V_MEA_G2") (class "Default")
      (node (ref "5V-NI2") (pin "TP") (pinfunction "P$1_TP") (pintype "bidirectional"))
      (node (ref "C53") (pin "1") (pinfunction "+_1") (pintype "passive"))
      (node (ref "C57") (pin "2") (pinfunction "2_2") (pintype "passive"))
      (node (ref "D13") (pin "A") (pinfunction "A_A") (pintype "passive"))
      (node (ref "IC11") (pin "1") (pinfunction "VDD_1") (pintype "power_in"))
      (node (ref "IC14") (pin "1") (pinfunction "VDD_1") (pintype "power_in"))
      (node (ref "IC16") (pin "1") (pinfunction "VDD_1") (pintype "power_in"))
      (node (ref "IC7") (pin "1") (pinfunction "VDD_1") (pintype "power_in"))
      (node (ref "J7") (pin "2") (pinfunction "2_2") (pintype "passive"))
      (node (ref "L5") (pin "2") (pinfunction "2_2") (pintype "passive"))
      (node (ref "R108") (pin "1") (pinfunction "1_1") (pintype "passive"))
      (node (ref "R110") (pin "1") (pinfunction "1_1") (pintype "passive"))
      (node (ref "R110") (pin "2") (pinfunction "2_2") (pintype "passive"))
      (node (ref "R110") (pin "3") (pinfunction "3_3") (pintype "passive"))
      (node (ref "R110") (pin "4") (pinfunction "4_4") (pintype "passive"))
      (node (ref "R64") (pin "1") (pinfunction "1_1") (pintype "passive"))
      (node (ref "R64") (pin "2") (pinfunction "2_2") (pintype "passive"))
      (node (ref "R64") (pin "3") (pinfunction "3_3") (pintype "passive"))
      (node (ref "R64") (pin "4") (pinfunction "4_4") (pintype "passive"))
    )
    (net (code "5") (name "+12V") (class "Default")
      (node (ref "C1") (pin "1") (pinfunction "1_1") (pintype "passive"))
      (node (ref "C2") (pin "1") (pinfunction "1_1") (pintype "passive"))
      (node (ref "C3") (pin "1") (pinfunction "1_1") (pintype "passive"))
      (node (ref "C4") (pin "1") (pinfunction "1_1") (pintype "passive"))
      (node (ref "D1") (pin "C") (pinfunction "C_C") (pintype "passive"))
      (node (ref "D2") (pin "C") (pinfunction "C_C") (pintype "passive"))
      (node (ref "D3") (pin "C") (pinfunction "C_C") (pintype "passive"))
      (node (ref "D4") (pin "C") (pinfunction "C_C") (pintype "passive"))
      (node (ref "D5") (pin "C") (pinfunction "C_C") (pintype "passive"))
      (node (ref "D6") (pin "C") (pinfunction "C_C") (pintype "passive"))
      (node (ref "D7") (pin "C") (pinfunction "C_C") (pintype "passive"))
      (node (ref "D8") (pin "C") (pinfunction "C_C") (pintype "passive"))
      (node (ref "IC1") (pin "2") (pinfunction "IN_2") (pintype "bidirectional"))
      (node (ref "IC2") (pin "2") (pinfunction "IN_2") (pintype "bidirectional"))
      (node (ref "IC3") (pin "10") (pinfunction "COM_10") (pintype "bidirectional"))
      (node (ref "J10") (pin "1") (pinfunction "1_1") (pintype "passive"))
      (node (ref "J8") (pin "1") (pinfunction "1_1") (pintype "passive"))
      (node (ref "J9") (pin "1") (pinfunction "1_1") (pintype "passive"))
      (node (ref "K1") (pin "8") (pinfunction "8_8") (pintype "passive"))
      (node (ref "K2") (pin "8") (pinfunction "8_8") (pintype "passive"))
      (node (ref "K3") (pin "8") (pinfunction "8_8") (pintype "passive"))
      (node (ref "K4") (pin "8") (pinfunction "8_8") (pintype "passive"))
      (node (ref "K5") (pin "8") (pinfunction "8_8") (pintype "passive"))
      (node (ref "K6") (pin "8") (pinfunction "8_8") (pintype "passive"))
      (node (ref "K7") (pin "8") (pinfunction "8_8") (pintype "passive"))
      (node (ref "K8") (pin "8") (pinfunction "8_8") (pintype "passive"))
      (node (ref "R1") (pin "1") (pinfunction "1_1") (pintype "passive"))
      (node (ref "R2") (pin "1") (pinfunction "1_1") (pintype "passive"))
      (node (ref "R94") (pin "2") (pinfunction "2_2") (pintype "passive"))
    )
    (net (code "6") (name "+12V_MEA") (class "Default")
      (node (ref "J1") (pin "13") (pinfunction "13_13") (pintype "bidirectional"))
      (node (ref "R94") (pin "1") (pinfunction "1_1") (pintype "passive"))
      (node (ref "R95") (pin "2") (pinfunction "2_2") (pintype "passive"))
    )
    (net (code "7") (name "AC_L") (class "Default")
      (node (ref "AC/DC1") (pin "AC_L") (pinfunction "AC/L_AC_L") (pintype "input"))
      (node (ref "AC/DC2") (pin "AC/L") (pinfunction "AC/L_AC/L") (pintype "input"))
      (node (ref "AC_L") (pin "1") (pinfunction "KL_1") (pintype "passive"))
      (node (ref "AC_L") (pin "2") (pinfunction "KL_2") (pintype "passive"))
      (node (ref "K1") (pin "3") (pinfunction "3_3") (pintype "passive"))
      (node (ref "K1") (pin "6") (pinfunction "6_6") (pintype "passive"))
      (node (ref "K2") (pin "3") (pinfunction "3_3") (pintype "passive"))
      (node (ref "K2") (pin "6") (pinfunction "6_6") (pintype "passive"))
      (node (ref "K3") (pin "3") (pinfunction "3_3") (pintype "passive"))
      (node (ref "K3") (pin "6") (pinfunction "6_6") (pintype "passive"))
      (node (ref "K4") (pin "3") (pinfunction "3_3") (pintype "passive"))
      (node (ref "K4") (pin "6") (pinfunction "6_6") (pintype "passive"))
      (node (ref "K5") (pin "3") (pinfunction "3_3") (pintype "passive"))
      (node (ref "K5") (pin "6") (pinfunction "6_6") (pintype "passive"))
      (node (ref "K6") (pin "3") (pinfunction "3_3") (pintype "passive"))
      (node (ref "K6") (pin "6") (pinfunction "6_6") (pintype "passive"))
      (node (ref "K7") (pin "3") (pinfunction "3_3") (pintype "passive"))
      (node (ref "K7") (pin "6") (pinfunction "6_6") (pintype "passive"))
      (node (ref "K8") (pin "3") (pinfunction "3_3") (pintype "passive"))
      (node (ref "K8") (pin "6") (pinfunction "6_6") (pintype "passive"))
      (node (ref "R106") (pin "1") (pinfunction "1_1") (pintype "passive"))
      (node (ref "R62") (pin "1") (pinfunction "1_1") (pintype "passive"))
    )
    (net (code "8") (name "AC_N") (class "Default")
      (node (ref "AC/DC1") (pin "AC_N") (pinfunction "AC/N_AC_N") (pintype "input"))
      (node (ref "AC/DC2") (pin "AC/N") (pinfunction "AC/N_AC/N") (pintype "input"))
      (node (ref "AC_N") (pin "1") (pinfunction "KL_1") (pintype "passive"))
      (node (ref "AC_N") (pin "2") (pinfunction "KL_2") (pintype "passive"))
      (node (ref "R57") (pin "1") (pinfunction "1_1") (pintype "passive"))
      (node (ref "R58") (pin "1") (pinfunction "1_1") (pintype "passive"))
      (node (ref "R59") (pin "1") (pinfunction "1_1") (pintype "passive"))
    )
    (net (code "9") (name "AGND") (class "Default")
      (node (ref "C23") (pin "2") (pinfunction "-_2") (pintype "passive"))
      (node (ref "C24") (pin "2") (pinfunction "2_2") (pintype "passive"))
      (node (ref "C25") (pin "2") (pinfunction "2_2") (pintype "passive"))
      (node (ref "C26") (pin "2") (pinfunction "2_2") (pintype "passive"))
      (node (ref "C27") (pin "2") (pinfunction "2_2") (pintype "passive"))
      (node (ref "C28") (pin "2") (pinfunction "2_2") (pintype "passive"))
      (node (ref "C29") (pin "2") (pinfunction "2_2") (pintype "passive"))
      (node (ref "C30") (pin "2") (pinfunction "2_2") (pintype "passive"))
      (node (ref "C31") (pin "2") (pinfunction "2_2") (pintype "passive"))
      (node (ref "C32") (pin "2") (pinfunction "2_2") (pintype "passive"))
      (node (ref "C35") (pin "1") (pinfunction "-_1") (pintype "passive"))
      (node (ref "C36") (pin "2") (pinfunction "2_2") (pintype "passive"))
      (node (ref "C37") (pin "2") (pinfunction "2_2") (pintype "passive"))
      (node (ref "C38") (pin "2") (pinfunction "2_2") (pintype "passive"))
      (node (ref "C39") (pin "2") (pinfunction "2_2") (pintype "passive"))
      (node (ref "C40") (pin "2") (pinfunction "2_2") (pintype "passive"))
      (node (ref "C41") (pin "2") (pinfunction "2_2") (pintype "passive"))
      (node (ref "C42") (pin "2") (pinfunction "2_2") (pintype "passive"))
      (node (ref "C43") (pin "2") (pinfunction "2_2") (pintype "passive"))
      (node (ref "C44") (pin "2") (pinfunction "2_2") (pintype "passive"))
      (node (ref "C45") (pin "1") (pinfunction "1_1") (pintype "passive"))
      (node (ref "C47") (pin "1") (pinfunction "-_1") (pintype "passive"))
      (node (ref "C48") (pin "2") (pinfunction "2_2") (pintype "passive"))
      (node (ref "C49") (pin "2") (pinfunction "2_2") (pintype "passive"))
      (node (ref "C50") (pin "2") (pinfunction "2_2") (pintype "passive"))
      (node (ref "C53") (pin "2") (pinfunction "-_2") (pintype "passive"))
      (node (ref "C54") (pin "2") (pinfunction "2_2") (pintype "passive"))
      (node (ref "C55") (pin "2") (pinfunction "2_2") (pintype "passive"))
      (node (ref "C56") (pin "2") (pinfunction "2_2") (pintype "passive"))
      (node (ref "C57") (pin "1") (pinfunction "1_1") (pintype "passive"))
      (node (ref "D11") (pin "A") (pinfunction "A_A") (pintype "passive"))
      (node (ref "D14") (pin "A") (pinfunction "A_A") (pintype "passive"))
      (node (ref "IC10") (pin "5") (pinfunction "GND_5") (pintype "power_in"))
      (node (ref "IC11") (pin "5") (pinfunction "GND_5") (pintype "power_in"))
      (node (ref "IC12") (pin "5") (pinfunction "GND_5") (pintype "power_in"))
      (node (ref "IC14") (pin "5") (pinfunction "GND_5") (pintype "power_in"))
      (node (ref "IC16") (pin "5") (pinfunction "GND_5") (pintype "power_in"))
      (node (ref "IC6") (pin "5") (pinfunction "GND_5") (pintype "power_in"))
      (node (ref "IC7") (pin "5") (pinfunction "GND_5") (pintype "power_in"))
      (node (ref "IC8") (pin "5") (pinfunction "GND_5") (pintype "power_in"))
      (node (ref "R104") (pin "2") (pinfunction "2_2") (pintype "passive"))
      (node (ref "R108") (pin "2") (pinfunction "2_2") (pintype "passive"))
      (node (ref "R120") (pin "2") (pinfunction "2_2") (pintype "passive"))
      (node (ref "R40") (pin "2") (pinfunction "2_2") (pintype "passive"))
      (node (ref "R48") (pin "2") (pinfunction "2_2") (pintype "passive"))
      (node (ref "R56") (pin "2") (pinfunction "2_2") (pintype "passive"))
      (node (ref "R57") (pin "2") (pinfunction "2_2") (pintype "passive"))
      (node (ref "R58") (pin "2") (pinfunction "2_2") (pintype "passive"))
      (node (ref "R59") (pin "2") (pinfunction "2_2") (pintype "passive"))
      (node (ref "R72") (pin "2") (pinfunction "2_2") (pintype "passive"))
      (node (ref "R80") (pin "2") (pinfunction "2_2") (pintype "passive"))
      (node (ref "R88") (pin "2") (pinfunction "2_2") (pintype "passive"))
      (node (ref "R96") (pin "2") (pinfunction "2_2") (pintype "passive"))
    )
    (net (code "10") (name "C13_IN1") (class "Default")
      (node (ref "R25") (pin "2") (pinfunction "2_2") (pintype "passive"))
      (node (ref "R33") (pin "1") (pinfunction "1_1") (pintype "passive"))
      (node (ref "R35") (pin "2") (pinfunction "2_2") (pintype "passive"))
    )
    (net (code "11") (name "C13_IN2") (class "Default")
      (node (ref "R32") (pin "2") (pinfunction "2_2") (pintype "passive"))
      (node (ref "R49") (pin "1") (pinfunction "1_1") (pintype "passive"))
      (node (ref "R51") (pin "2") (pinfunction "2_2") (pintype "passive"))
    )
    (net (code "12") (name "C13_IN3") (class "Default")
      (node (ref "R31") (pin "2") (pinfunction "2_2") (pintype "passive"))
      (node (ref "R65") (pin "1") (pinfunction "1_1") (pintype "passive"))
      (node (ref "R67") (pin "2") (pinfunction "2_2") (pintype "passive"))
    )
    (net (code "13") (name "C13_IN4") (class "Default")
      (node (ref "R30") (pin "2") (pinfunction "2_2") (pintype "passive"))
      (node (ref "R81") (pin "1") (pinfunction "1_1") (pintype "passive"))
      (node (ref "R83") (pin "2") (pinfunction "2_2") (pintype "passive"))
    )
    (net (code "14") (name "C13_IN5") (class "Default")
      (node (ref "R26") (pin "2") (pinfunction "2_2") (pintype "passive"))
      (node (ref "R41") (pin "1") (pinfunction "1_1") (pintype "passive"))
      (node (ref "R43") (pin "2") (pinfunction "2_2") (pintype "passive"))
    )
    (net (code "15") (name "C13_IN6") (class "Default")
      (node (ref "R27") (pin "2") (pinfunction "2_2") (pintype "passive"))
      (node (ref "R73") (pin "1") (pinfunction "1_1") (pintype "passive"))
      (node (ref "R75") (pin "2") (pinfunction "2_2") (pintype "passive"))
    )
    (net (code "16") (name "C13_IN7") (class "Default")
      (node (ref "R28") (pin "2") (pinfunction "2_2") (pintype "passive"))
      (node (ref "R97") (pin "1") (pinfunction "1_1") (pintype "passive"))
      (node (ref "R99") (pin "2") (pinfunction "2_2") (pintype "passive"))
    )
    (net (code "17") (name "C13_IN8") (class "Default")
      (node (ref "R113") (pin "1") (pinfunction "1_1") (pintype "passive"))
      (node (ref "R115") (pin "2") (pinfunction "2_2") (pintype "passive"))
      (node (ref "R29") (pin "2") (pinfunction "2_2") (pintype "passive"))
    )
    (net (code "18") (name "GND") (class "Default")
      (node (ref "AC/DC1") (pin "-V") (pinfunction "-V_-V") (pintype "output"))
      (node (ref "AC/DC2") (pin "-V") (pinfunction "-V_-V") (pintype "output"))
      (node (ref "C1") (pin "2") (pinfunction "2_2") (pintype "passive"))
      (node (ref "C10") (pin "2") (pinfunction "2_2") (pintype "passive"))
      (node (ref "C13") (pin "2") (pinfunction "2_2") (pintype "passive"))
      (node (ref "C14") (pin "2") (pinfunction "2_2") (pintype "passive"))
      (node (ref "C15") (pin "2") (pinfunction "2_2") (pintype "passive"))
      (node (ref "C16") (pin "2") (pinfunction "2_2") (pintype "passive"))
      (node (ref "C17") (pin "2") (pinfunction "2_2") (pintype "passive"))
      (node (ref "C18") (pin "2") (pinfunction "2_2") (pintype "passive"))
      (node (ref "C19") (pin "2") (pinfunction "2_2") (pintype "passive"))
      (node (ref "C2") (pin "2") (pinfunction "2_2") (pintype "passive"))
      (node (ref "C20") (pin "2") (pinfunction "2_2") (pintype "passive"))
      (node (ref "C3") (pin "2") (pinfunction "2_2") (pintype "passive"))
      (node (ref "C33") (pin "2") (pinfunction "2_2") (pintype "passive"))
      (node (ref "C34") (pin "2") (pinfunction "2_2") (pintype "passive"))
      (node (ref "C4") (pin "2") (pinfunction "2_2") (pintype "passive"))
      (node (ref "C6") (pin "2") (pinfunction "2_2") (pintype "passive"))
      (node (ref "C7") (pin "2") (pinfunction "2_2") (pintype "passive"))
      (node (ref "GND") (pin "TP") (pinfunction "P$1_TP") (pintype "bidirectional"))
      (node (ref "GND-3") (pin "TP") (pinfunction "P$1_TP") (pintype "bidirectional"))
      (node (ref "GND-5") (pin "TP") (pinfunction "P$1_TP") (pintype "bidirectional"))
      (node (ref "IC1") (pin "4") (pinfunction "GND_4") (pintype "bidirectional"))
      (node (ref "IC2") (pin "4") (pinfunction "GND_4") (pintype "bidirectional"))
      (node (ref "IC3") (pin "9") (pinfunction "GND_9") (pintype "bidirectional"))
      (node (ref "IC4") (pin "11") (pinfunction "A0_11") (pintype "bidirectional"))
      (node (ref "IC4") (pin "12") (pinfunction "A1_12") (pintype "bidirectional"))
      (node (ref "IC4") (pin "13") (pinfunction "A2_13") (pintype "bidirectional"))
      (node (ref "IC4") (pin "6") (pinfunction "VSS_6") (pintype "bidirectional"))
      (node (ref "IC4") (pin "PAD") (pinfunction "VSS_PAD") (pintype "bidirectional"))
      (node (ref "IC9") (pin "8") (pinfunction "GND_8") (pintype "power_in"))
      (node (ref "J1") (pin "12") (pinfunction "12_12") (pintype "bidirectional"))
      (node (ref "J1") (pin "14") (pinfunction "14_14") (pintype "bidirectional"))
      (node (ref "J1") (pin "16") (pinfunction "16_16") (pintype "bidirectional"))
      (node (ref "J1") (pin "9") (pinfunction "9_9") (pintype "bidirectional"))
      (node (ref "J1") (pin "Z0") (pinfunction "Z1_Z0") (pintype "bidirectional"))
      (node (ref "J1") (pin "Z1") (pinfunction "Z1_Z1") (pintype "bidirectional"))
      (node (ref "J1") (pin "Z2") (pinfunction "Z2_Z2") (pintype "bidirectional"))
      (node (ref "J1") (pin "Z3") (pinfunction "Z3_Z3") (pintype "bidirectional"))
      (node (ref "J1") (pin "Z4") (pinfunction "Z3_Z4") (pintype "bidirectional"))
      (node (ref "J1") (pin "Z5") (pinfunction "Z4_Z5") (pintype "bidirectional"))
      (node (ref "OPT1") (pin "11") (pinfunction "11_11") (pintype "passive"))
      (node (ref "OPT1") (pin "13") (pinfunction "13_13") (pintype "passive"))
      (node (ref "OPT1") (pin "15") (pinfunction "15_15") (pintype "passive"))
      (node (ref "OPT1") (pin "9") (pinfunction "9_9") (pintype "passive"))
      (node (ref "OPT2") (pin "5") (pinfunction "5_5") (pintype "passive"))
      (node (ref "OPT2") (pin "7") (pinfunction "7_7") (pintype "passive"))
      (node (ref "OPT3") (pin "5") (pinfunction "5_5") (pintype "passive"))
      (node (ref "OPT3") (pin "7") (pinfunction "7_7") (pintype "passive"))
      (node (ref "R12") (pin "2") (pinfunction "2_2") (pintype "passive"))
      (node (ref "R14") (pin "2") (pinfunction "2_2") (pintype "passive"))
      (node (ref "R4") (pin "2") (pinfunction "2_2") (pintype "passive"))
      (node (ref "R6") (pin "2") (pinfunction "2_2") (pintype "passive"))
      (node (ref "R95") (pin "1") (pinfunction "1_1") (pintype "passive"))
      (node (ref "Z1") (pin "A") (pinfunction "A_A") (pintype "passive"))
    )
    (net (code "19") (name "I2C_SCL") (class "Default")
      (node (ref "IC4") (pin "8") (pinfunction "SCL_8") (pintype "bidirectional"))
      (node (ref "J1") (pin "8") (pinfunction "8_8") (pintype "bidirectional"))
    )
    (net (code "20") (name "I2C_SDA") (class "Default")
      (node (ref "IC4") (pin "9") (pinfunction "SDA_9") (pintype "bidirectional"))
      (node (ref "J1") (pin "7") (pinfunction "7_7") (pintype "bidirectional"))
    )
    (net (code "21") (name "MCP_REL_RST") (class "Default")
      (node (ref "IC4") (pin "14") (pinfunction "~{RESET}_14") (pintype "bidirectional"))
      (node (ref "J1") (pin "15") (pinfunction "15_15") (pintype "bidirectional"))
    )
    (net (code "22") (name "MUX_A") (class "Default")
      (node (ref "IC4") (pin "25") (pinfunction "IO2.0_25") (pintype "bidirectional"))
      (node (ref "IC9") (pin "11") (pinfunction "A_11") (pintype "input"))
      (node (ref "R93") (pin "4") (pinfunction "4_4") (pintype "passive"))
    )
    (net (code "23") (name "MUX_B") (class "Default")
      (node (ref "IC4") (pin "26") (pinfunction "IO2.1_26") (pintype "bidirectional"))
      (node (ref "IC9") (pin "10") (pinfunction "B_10") (pintype "input"))
      (node (ref "R93") (pin "3") (pinfunction "3_3") (pintype "passive"))
    )
    (net (code "24") (name "MUX_C") (class "Default")
      (node (ref "IC4") (pin "27") (pinfunction "IO2.2_27") (pintype "bidirectional"))
      (node (ref "IC9") (pin "9") (pinfunction "C_9") (pintype "input"))
      (node (ref "R93") (pin "2") (pinfunction "2_2") (pintype "passive"))
    )
    (net (code "25") (name "MUX_EN") (class "Default")
      (node (ref "IC4") (pin "28") (pinfunction "IO2.3_28") (pintype "bidirectional"))
      (node (ref "IC9") (pin "7") (pinfunction "~{EN}_7") (pintype "input"))
      (node (ref "R93") (pin "1") (pinfunction "1_1") (pintype "passive"))
    )
    (net (code "26") (name "Net-(3VFB-P$1)") (class "Default")
      (node (ref "3VFB") (pin "TP") (pinfunction "P$1_TP") (pintype "bidirectional"))
      (node (ref "C12") (pin "2") (pinfunction "2_2") (pintype "passive"))
      (node (ref "R10") (pin "2") (pinfunction "2_2") (pintype "passive"))
      (node (ref "R13") (pin "2") (pinfunction "2_2") (pintype "passive"))
      (node (ref "R14") (pin "1") (pinfunction "1_1") (pintype "passive"))
    )
    (net (code "27") (name "Net-(5VFB-P$1)") (class "Default")
      (node (ref "5VFB") (pin "TP") (pinfunction "P$1_TP") (pintype "bidirectional"))
      (node (ref "C11") (pin "2") (pinfunction "2_2") (pintype "passive"))
      (node (ref "R11") (pin "2") (pinfunction "2_2") (pintype "passive"))
      (node (ref "R12") (pin "1") (pinfunction "1_1") (pintype "passive"))
      (node (ref "R8") (pin "2") (pinfunction "2_2") (pintype "passive"))
    )
    (net (code "28") (name "Net-(12VDC-P$1)") (class "Default")
      (node (ref "12VDC") (pin "TP") (pinfunction "P$1_TP") (pintype "bidirectional"))
      (node (ref "AC/DC1") (pin "+V") (pinfunction "+V_+V") (pintype "output"))
      (node (ref "AC/DC2") (pin "+V") (pinfunction "+V_+V") (pintype "output"))
      (node (ref "C10") (pin "1") (pinfunction "1_1") (pintype "passive"))
      (node (ref "C13") (pin "1") (pinfunction "1_1") (pintype "passive"))
      (node (ref "C16") (pin "1") (pinfunction "1_1") (pintype "passive"))
      (node (ref "J10") (pin "2") (pinfunction "2_2") (pintype "passive"))
      (node (ref "J8") (pin "2") (pinfunction "2_2") (pintype "passive"))
      (node (ref "J9") (pin "2") (pinfunction "2_2") (pintype "passive"))
      (node (ref "Z1") (pin "C") (pinfunction "C_C") (pintype "passive"))
    )
    (net (code "29") (name "Net-(C8-Pad1)") (class "Default")
      (node (ref "C8") (pin "1") (pinfunction "1_1") (pintype "passive"))
      (node (ref "R7") (pin "1") (pinfunction "1_1") (pintype "passive"))
    )
    (net (code "30") (name "Net-(C9-Pad1)") (class "Default")
      (node (ref "C9") (pin "1") (pinfunction "1_1") (pintype "passive"))
      (node (ref "R9") (pin "1") (pinfunction "1_1") (pintype "passive"))
    )
    (net (code "31") (name "Net-(C22-Pad2)") (class "Default")
      (node (ref "C22") (pin "2") (pinfunction "2_2") (pintype "passive"))
      (node (ref "D9") (pin "C") (pinfunction "C_C") (pintype "passive"))
      (node (ref "R61") (pin "1") (pinfunction "1_1") (pintype "passive"))
    )
    (net (code "32") (name "Net-(C35-+)") (class "Default")
      (node (ref "C35") (pin "2") (pinfunction "+_2") (pintype "passive"))
      (node (ref "D10") (pin "C") (pinfunction "C_C") (pintype "passive"))
      (node (ref "IC13") (pin "5") (pinfunction "DRAIN_5") (pintype "input"))
      (node (ref "L-REC1") (pin "TP") (pinfunction "P$1_TP") (pintype "bidirectional"))
    )
    (net (code "33") (name "Net-(C47-+)") (class "Default")
      (node (ref "C47") (pin "2") (pinfunction "+_2") (pintype "passive"))
      (node (ref "D12") (pin "C") (pinfunction "C_C") (pintype "passive"))
      (node (ref "IC5") (pin "5") (pinfunction "DRAIN_5") (pintype "input"))
      (node (ref "L-REC2") (pin "TP") (pinfunction "P$1_TP") (pintype "bidirectional"))
    )
    (net (code "34") (name "Net-(C52-Pad2)") (class "Default")
      (node (ref "C52") (pin "2") (pinfunction "2_2") (pintype "passive"))
      (node (ref "D13") (pin "C") (pinfunction "C_C") (pintype "passive"))
      (node (ref "R105") (pin "1") (pinfunction "1_1") (pintype "passive"))
    )
    (net (code "35") (name "Net-(D10-PadA)") (class "Default")
      (node (ref "D10") (pin "A") (pinfunction "A_A") (pintype "passive"))
      (node (ref "R62") (pin "2") (pinfunction "2_2") (pintype "passive"))
    )
    (net (code "36") (name "Net-(D12-PadA)") (class "Default")
      (node (ref "D12") (pin "A") (pinfunction "A_A") (pintype "passive"))
      (node (ref "R106") (pin "2") (pinfunction "2_2") (pintype "passive"))
    )
    (net (code "37") (name "Net-(FB-NI1-P$1)") (class "Default")
      (node (ref "C5") (pin "2") (pinfunction "2_2") (pintype "passive"))
      (node (ref "FB-NI1") (pin "TP") (pinfunction "P$1_TP") (pintype "bidirectional"))
      (node (ref "IC13") (pin "2") (pinfunction "FB_2") (pintype "input"))
      (node (ref "R60") (pin "1") (pinfunction "1_1") (pintype "passive"))
      (node (ref "R61") (pin "2") (pinfunction "2_2") (pintype "passive"))
    )
    (net (code "38") (name "Net-(FB-NI2-P$1)") (class "Default")
      (node (ref "C51") (pin "2") (pinfunction "2_2") (pintype "passive"))
      (node (ref "FB-NI2") (pin "TP") (pinfunction "P$1_TP") (pintype "bidirectional"))
      (node (ref "IC5") (pin "2") (pinfunction "FB_2") (pintype "input"))
      (node (ref "R105") (pin "2") (pinfunction "2_2") (pintype "passive"))
      (node (ref "R107") (pin "1") (pinfunction "1_1") (pintype "passive"))
    )
    (net (code "39") (name "Net-(IC1-AAM)") (class "Default")
      (node (ref "IC1") (pin "1") (pinfunction "AAM_1") (pintype "bidirectional"))
      (node (ref "R3") (pin "2") (pinfunction "2_2") (pintype "passive"))
      (node (ref "R4") (pin "1") (pinfunction "1_1") (pintype "passive"))
    )
    (net (code "40") (name "Net-(IC1-BST)") (class "Default")
      (node (ref "IC1") (pin "5") (pinfunction "BST_5") (pintype "bidirectional"))
      (node (ref "R7") (pin "2") (pinfunction "2_2") (pintype "passive"))
    )
    (net (code "41") (name "Net-(IC1-EN)") (class "Default")
      (node (ref "IC1") (pin "6") (pinfunction "EN_6") (pintype "bidirectional"))
      (node (ref "R1") (pin "2") (pinfunction "2_2") (pintype "passive"))
    )
    (net (code "42") (name "Net-(IC1-FB)") (class "Default")
      (node (ref "IC1") (pin "8") (pinfunction "FB_8") (pintype "bidirectional"))
      (node (ref "R8") (pin "1") (pinfunction "1_1") (pintype "passive"))
    )
    (net (code "43") (name "Net-(IC1-SW)") (class "Default")
      (node (ref "C8") (pin "2") (pinfunction "2_2") (pintype "passive"))
      (node (ref "IC1") (pin "3") (pinfunction "SW_3") (pintype "bidirectional"))
      (node (ref "L1") (pin "1") (pinfunction "1_1") (pintype "passive"))
      (node (ref "SW") (pin "TP") (pinfunction "P$1_TP") (pintype "bidirectional"))
    )
    (net (code "44") (name "Net-(IC1-VCC)") (class "Default")
      (node (ref "C6") (pin "1") (pinfunction "1_1") (pintype "passive"))
      (node (ref "IC1") (pin "7") (pinfunction "VCC_7") (pintype "bidirectional"))
      (node (ref "R3") (pin "1") (pinfunction "1_1") (pintype "passive"))
    )
    (net (code "45") (name "Net-(IC2-AAM)") (class "Default")
      (node (ref "IC2") (pin "1") (pinfunction "AAM_1") (pintype "bidirectional"))
      (node (ref "R5") (pin "2") (pinfunction "2_2") (pintype "passive"))
      (node (ref "R6") (pin "1") (pinfunction "1_1") (pintype "passive"))
    )
    (net (code "46") (name "Net-(IC2-BST)") (class "Default")
      (node (ref "IC2") (pin "5") (pinfunction "BST_5") (pintype "bidirectional"))
      (node (ref "R9") (pin "2") (pinfunction "2_2") (pintype "passive"))
    )
    (net (code "47") (name "Net-(IC2-EN)") (class "Default")
      (node (ref "IC2") (pin "6") (pinfunction "EN_6") (pintype "bidirectional"))
      (node (ref "R2") (pin "2") (pinfunction "2_2") (pintype "passive"))
    )
    (net (code "48") (name "Net-(IC2-FB)") (class "Default")
      (node (ref "IC2") (pin "8") (pinfunction "FB_8") (pintype "bidirectional"))
      (node (ref "R10") (pin "1") (pinfunction "1_1") (pintype "passive"))
    )
    (net (code "49") (name "Net-(IC2-SW)") (class "Default")
      (node (ref "C9") (pin "2") (pinfunction "2_2") (pintype "passive"))
      (node (ref "IC2") (pin "3") (pinfunction "SW_3") (pintype "bidirectional"))
      (node (ref "L2") (pin "1") (pinfunction "1_1") (pintype "passive"))
      (node (ref "SW3") (pin "TP") (pinfunction "P$1_TP") (pintype "bidirectional"))
    )
    (net (code "50") (name "Net-(IC2-VCC)") (class "Default")
      (node (ref "C7") (pin "1") (pinfunction "1_1") (pintype "passive"))
      (node (ref "IC2") (pin "7") (pinfunction "VCC_7") (pintype "bidirectional"))
      (node (ref "R5") (pin "1") (pinfunction "1_1") (pintype "passive"))
    )
    (net (code "51") (name "Net-(IC3-1C)") (class "Default")
      (node (ref "IC3") (pin "18") (pinfunction "1C_18") (pintype "bidirectional"))
      (node (ref "R17") (pin "1") (pinfunction "1_1") (pintype "passive"))
    )
    (net (code "52") (name "Net-(IC3-2C)") (class "Default")
      (node (ref "IC3") (pin "17") (pinfunction "2C_17") (pintype "bidirectional"))
      (node (ref "R18") (pin "1") (pinfunction "1_1") (pintype "passive"))
    )
    (net (code "53") (name "Net-(IC3-3C)") (class "Default")
      (node (ref "IC3") (pin "16") (pinfunction "3C_16") (pintype "bidirectional"))
      (node (ref "R19") (pin "1") (pinfunction "1_1") (pintype "passive"))
    )
    (net (code "54") (name "Net-(IC3-4C)") (class "Default")
      (node (ref "IC3") (pin "15") (pinfunction "4C_15") (pintype "bidirectional"))
      (node (ref "R20") (pin "1") (pinfunction "1_1") (pintype "passive"))
    )
    (net (code "55") (name "Net-(IC3-5C)") (class "Default")
      (node (ref "IC3") (pin "14") (pinfunction "5C_14") (pintype "bidirectional"))
      (node (ref "R21") (pin "1") (pinfunction "1_1") (pintype "passive"))
    )
    (net (code "56") (name "Net-(IC3-6C)") (class "Default")
      (node (ref "IC3") (pin "13") (pinfunction "6C_13") (pintype "bidirectional"))
      (node (ref "R22") (pin "1") (pinfunction "1_1") (pintype "passive"))
    )
    (net (code "57") (name "Net-(IC3-7C)") (class "Default")
      (node (ref "IC3") (pin "12") (pinfunction "7C_12") (pintype "bidirectional"))
      (node (ref "R23") (pin "1") (pinfunction "1_1") (pintype "passive"))
    )
    (net (code "58") (name "Net-(IC3-8C)") (class "Default")
      (node (ref "IC3") (pin "11") (pinfunction "8C_11") (pintype "bidirectional"))
      (node (ref "R24") (pin "1") (pinfunction "1_1") (pintype "passive"))
    )
    (net (code "59") (name "Net-(IC5-SRC)") (class "Default")
      (node (ref "C46") (pin "1") (pinfunction "1_1") (pintype "passive"))
      (node (ref "C51") (pin "1") (pinfunction "1_1") (pintype "passive"))
      (node (ref "C52") (pin "1") (pinfunction "1_1") (pintype "passive"))
      (node (ref "D14") (pin "C") (pinfunction "C_C") (pintype "passive"))
      (node (ref "IC5") (pin "3") (pinfunction "SRC2_3") (pintype "output"))
      (node (ref "IC5") (pin "4") (pinfunction "SRC_4") (pintype "output"))
      (node (ref "L5") (pin "1") (pinfunction "1_1") (pintype "passive"))
      (node (ref "R107") (pin "2") (pinfunction "2_2") (pintype "passive"))
    )
    (net (code "60") (name "Net-(IC5-VCC)") (class "Default")
      (node (ref "C46") (pin "2") (pinfunction "2_2") (pintype "passive"))
      (node (ref "IC5") (pin "1") (pinfunction "VCC_1") (pintype "output"))
      (node (ref "VNI2") (pin "TP") (pinfunction "P$1_TP") (pintype "bidirectional"))
    )
    (net (code "61") (name "Net-(IC6-INN)") (class "Default")
      (node (ref "C25") (pin "1") (pinfunction "1_1") (pintype "passive"))
      (node (ref "IC6") (pin "3") (pinfunction "INN_3") (pintype "input"))
      (node (ref "R34") (pin "2") (pinfunction "2_2") (pintype "passive"))
    )
    (net (code "62") (name "Net-(IC6-INP)") (class "Default")
      (node (ref "C24") (pin "1") (pinfunction "1_1") (pintype "passive"))
      (node (ref "IC6") (pin "2") (pinfunction "INP_2") (pintype "input"))
      (node (ref "R33") (pin "2") (pinfunction "2_2") (pintype "passive"))
    )
    (net (code "63") (name "Net-(IC6-VP)") (class "Default")
      (node (ref "C26") (pin "1") (pinfunction "1_1") (pintype "passive"))
      (node (ref "IC6") (pin "4") (pinfunction "VP_4") (pintype "input"))
      (node (ref "R39") (pin "2") (pinfunction "2_2") (pintype "passive"))
      (node (ref "R40") (pin "1") (pinfunction "1_1") (pintype "passive"))
    )
    (net (code "64") (name "Net-(IC7-INN)") (class "Default")
      (node (ref "C28") (pin "1") (pinfunction "1_1") (pintype "passive"))
      (node (ref "IC7") (pin "3") (pinfunction "INN_3") (pintype "input"))
      (node (ref "R42") (pin "2") (pinfunction "2_2") (pintype "passive"))
    )
    (net (code "65") (name "Net-(IC7-INP)") (class "Default")
      (node (ref "C27") (pin "1") (pinfunction "1_1") (pintype "passive"))
      (node (ref "IC7") (pin "2") (pinfunction "INP_2") (pintype "input"))
      (node (ref "R41") (pin "2") (pinfunction "2_2") (pintype "passive"))
    )
    (net (code "66") (name "Net-(IC7-VP)") (class "Default")
      (node (ref "C29") (pin "1") (pinfunction "1_1") (pintype "passive"))
      (node (ref "IC7") (pin "4") (pinfunction "VP_4") (pintype "input"))
      (node (ref "R47") (pin "2") (pinfunction "2_2") (pintype "passive"))
      (node (ref "R48") (pin "1") (pinfunction "1_1") (pintype "passive"))
    )
    (net (code "67") (name "Net-(IC8-INN)") (class "Default")
      (node (ref "C31") (pin "1") (pinfunction "1_1") (pintype "passive"))
      (node (ref "IC8") (pin "3") (pinfunction "INN_3") (pintype "input"))
      (node (ref "R50") (pin "2") (pinfunction "2_2") (pintype "passive"))
    )
    (net (code "68") (name "Net-(IC8-INP)") (class "Default")
      (node (ref "C30") (pin "1") (pinfunction "1_1") (pintype "passive"))
      (node (ref "IC8") (pin "2") (pinfunction "INP_2") (pintype "input"))
      (node (ref "R49") (pin "2") (pinfunction "2_2") (pintype "passive"))
    )
    (net (code "69") (name "Net-(IC8-VP)") (class "Default")
      (node (ref "C32") (pin "1") (pinfunction "1_1") (pintype "passive"))
      (node (ref "IC8") (pin "4") (pinfunction "VP_4") (pintype "input"))
      (node (ref "R55") (pin "2") (pinfunction "2_2") (pintype "passive"))
      (node (ref "R56") (pin "1") (pinfunction "1_1") (pintype "passive"))
    )
    (net (code "70") (name "Net-(IC9-Y)") (class "Default")
      (node (ref "IC9") (pin "5") (pinfunction "Y_5") (pintype "bidirectional"))
      (node (ref "R91") (pin "1") (pinfunction "1_1") (pintype "passive"))
    )
    (net (code "71") (name "Net-(IC9-~{Y})") (class "Default")
      (node (ref "IC9") (pin "6") (pinfunction "~{Y}_6") (pintype "bidirectional"))
      (node (ref "R92") (pin "1") (pinfunction "1_1") (pintype "passive"))
    )
    (net (code "72") (name "Net-(IC10-INN)") (class "Default")
      (node (ref "C37") (pin "1") (pinfunction "1_1") (pintype "passive"))
      (node (ref "IC10") (pin "3") (pinfunction "INN_3") (pintype "input"))
      (node (ref "R66") (pin "2") (pinfunction "2_2") (pintype "passive"))
    )
    (net (code "73") (name "Net-(IC10-INP)") (class "Default")
      (node (ref "C36") (pin "1") (pinfunction "1_1") (pintype "passive"))
      (node (ref "IC10") (pin "2") (pinfunction "INP_2") (pintype "input"))
      (node (ref "R65") (pin "2") (pinfunction "2_2") (pintype "passive"))
    )
    (net (code "74") (name "Net-(IC10-VP)") (class "Default")
      (node (ref "C38") (pin "1") (pinfunction "1_1") (pintype "passive"))
      (node (ref "IC10") (pin "4") (pinfunction "VP_4") (pintype "input"))
      (node (ref "R71") (pin "2") (pinfunction "2_2") (pintype "passive"))
      (node (ref "R72") (pin "1") (pinfunction "1_1") (pintype "passive"))
    )
    (net (code "75") (name "Net-(IC11-INN)") (class "Default")
      (node (ref "C40") (pin "1") (pinfunction "1_1") (pintype "passive"))
      (node (ref "IC11") (pin "3") (pinfunction "INN_3") (pintype "input"))
      (node (ref "R74") (pin "2") (pinfunction "2_2") (pintype "passive"))
    )
    (net (code "76") (name "Net-(IC11-INP)") (class "Default")
      (node (ref "C39") (pin "1") (pinfunction "1_1") (pintype "passive"))
      (node (ref "IC11") (pin "2") (pinfunction "INP_2") (pintype "input"))
      (node (ref "R73") (pin "2") (pinfunction "2_2") (pintype "passive"))
    )
    (net (code "77") (name "Net-(IC11-VP)") (class "Default")
      (node (ref "C41") (pin "1") (pinfunction "1_1") (pintype "passive"))
      (node (ref "IC11") (pin "4") (pinfunction "VP_4") (pintype "input"))
      (node (ref "R79") (pin "2") (pinfunction "2_2") (pintype "passive"))
      (node (ref "R80") (pin "1") (pinfunction "1_1") (pintype "passive"))
    )
    (net (code "78") (name "Net-(IC12-INN)") (class "Default")
      (node (ref "C43") (pin "1") (pinfunction "1_1") (pintype "passive"))
      (node (ref "IC12") (pin "3") (pinfunction "INN_3") (pintype "input"))
      (node (ref "R82") (pin "2") (pinfunction "2_2") (pintype "passive"))
    )
    (net (code "79") (name "Net-(IC12-INP)") (class "Default")
      (node (ref "C42") (pin "1") (pinfunction "1_1") (pintype "passive"))
      (node (ref "IC12") (pin "2") (pinfunction "INP_2") (pintype "input"))
      (node (ref "R81") (pin "2") (pinfunction "2_2") (pintype "passive"))
    )
    (net (code "80") (name "Net-(IC12-VP)") (class "Default")
      (node (ref "C44") (pin "1") (pinfunction "1_1") (pintype "passive"))
      (node (ref "IC12") (pin "4") (pinfunction "VP_4") (pintype "input"))
      (node (ref "R87") (pin "2") (pinfunction "2_2") (pintype "passive"))
      (node (ref "R88") (pin "1") (pinfunction "1_1") (pintype "passive"))
    )
    (net (code "81") (name "Net-(IC13-SRC)") (class "Default")
      (node (ref "C21") (pin "1") (pinfunction "1_1") (pintype "passive"))
      (node (ref "C22") (pin "1") (pinfunction "1_1") (pintype "passive"))
      (node (ref "C5") (pin "1") (pinfunction "1_1") (pintype "passive"))
      (node (ref "D11") (pin "C") (pinfunction "C_C") (pintype "passive"))
      (node (ref "IC13") (pin "3") (pinfunction "SRC2_3") (pintype "output"))
      (node (ref "IC13") (pin "4") (pinfunction "SRC_4") (pintype "output"))
      (node (ref "L3") (pin "1") (pinfunction "1_1") (pintype "passive"))
      (node (ref "R60") (pin "2") (pinfunction "2_2") (pintype "passive"))
    )
    (net (code "82") (name "Net-(IC13-VCC)") (class "Default")
      (node (ref "C21") (pin "2") (pinfunction "2_2") (pintype "passive"))
      (node (ref "IC13") (pin "1") (pinfunction "VCC_1") (pintype "output"))
      (node (ref "VNI1") (pin "TP") (pinfunction "P$1_TP") (pintype "bidirectional"))
    )
    (net (code "83") (name "Net-(IC14-INN)") (class "Default")
      (node (ref "C49") (pin "1") (pinfunction "1_1") (pintype "passive"))
      (node (ref "IC14") (pin "3") (pinfunction "INN_3") (pintype "input"))
      (node (ref "R98") (pin "2") (pinfunction "2_2") (pintype "passive"))
    )
    (net (code "84") (name "Net-(IC14-INP)") (class "Default")
      (node (ref "C48") (pin "1") (pinfunction "1_1") (pintype "passive"))
      (node (ref "IC14") (pin "2") (pinfunction "INP_2") (pintype "input"))
      (node (ref "R97") (pin "2") (pinfunction "2_2") (pintype "passive"))
    )
    (net (code "85") (name "Net-(IC14-VP)") (class "Default")
      (node (ref "C50") (pin "1") (pinfunction "1_1") (pintype "passive"))
      (node (ref "IC14") (pin "4") (pinfunction "VP_4") (pintype "input"))
      (node (ref "R103") (pin "2") (pinfunction "2_2") (pintype "passive"))
      (node (ref "R104") (pin "1") (pinfunction "1_1") (pintype "passive"))
    )
    (net (code "86") (name "Net-(IC16-INN)") (class "Default")
      (node (ref "C55") (pin "1") (pinfunction "1_1") (pintype "passive"))
      (node (ref "IC16") (pin "3") (pinfunction "INN_3") (pintype "input"))
      (node (ref "R114") (pin "2") (pinfunction "2_2") (pintype "passive"))
    )
    (net (code "87") (name "Net-(IC16-INP)") (class "Default")
      (node (ref "C54") (pin "1") (pinfunction "1_1") (pintype "passive"))
      (node (ref "IC16") (pin "2") (pinfunction "INP_2") (pintype "input"))
      (node (ref "R113") (pin "2") (pinfunction "2_2") (pintype "passive"))
    )
    (net (code "88") (name "Net-(IC16-VP)") (class "Default")
      (node (ref "C56") (pin "1") (pinfunction "1_1") (pintype "passive"))
      (node (ref "IC16") (pin "4") (pinfunction "VP_4") (pintype "input"))
      (node (ref "R119") (pin "2") (pinfunction "2_2") (pintype "passive"))
      (node (ref "R120") (pin "1") (pinfunction "1_1") (pintype "passive"))
    )
    (net (code "89") (name "Net-(OPT1-Pad1)") (class "Default")
      (node (ref "OPT1") (pin "1") (pinfunction "1_1") (pintype "passive"))
      (node (ref "R63") (pin "8") (pinfunction "8_8") (pintype "passive"))
    )
    (net (code "90") (name "Net-(OPT1-Pad3)") (class "Default")
      (node (ref "OPT1") (pin "3") (pinfunction "3_3") (pintype "passive"))
      (node (ref "R63") (pin "7") (pinfunction "7_7") (pintype "passive"))
    )
    (net (code "91") (name "Net-(OPT1-Pad5)") (class "Default")
      (node (ref "OPT1") (pin "5") (pinfunction "5_5") (pintype "passive"))
      (node (ref "R63") (pin "6") (pinfunction "6_6") (pintype "passive"))
    )
    (net (code "92") (name "Net-(OPT1-Pad7)") (class "Default")
      (node (ref "OPT1") (pin "7") (pinfunction "7_7") (pintype "passive"))
      (node (ref "R63") (pin "5") (pinfunction "5_5") (pintype "passive"))
    )
    (net (code "93") (name "Net-(OPT2-Pad1)") (class "Default")
      (node (ref "OPT2") (pin "1") (pinfunction "1_1") (pintype "passive"))
      (node (ref "R110") (pin "8") (pinfunction "8_8") (pintype "passive"))
    )
    (net (code "94") (name "Net-(OPT2-Pad3)") (class "Default")
      (node (ref "OPT2") (pin "3") (pinfunction "3_3") (pintype "passive"))
      (node (ref "R110") (pin "7") (pinfunction "7_7") (pintype "passive"))
    )
    (net (code "95") (name "Net-(OPT3-Pad1)") (class "Default")
      (node (ref "OPT3") (pin "1") (pinfunction "1_1") (pintype "passive"))
      (node (ref "R64") (pin "8") (pinfunction "8_8") (pintype "passive"))
    )
    (net (code "96") (name "Net-(OPT3-Pad3)") (class "Default")
      (node (ref "OPT3") (pin "3") (pinfunction "3_3") (pintype "passive"))
      (node (ref "R64") (pin "7") (pinfunction "7_7") (pintype "passive"))
    )
    (net (code "97") (name "Net-(R36-Pad2)") (class "Default")
      (node (ref "R36") (pin "2") (pinfunction "2_2") (pintype "passive"))
      (node (ref "R37") (pin "1") (pinfunction "1_1") (pintype "passive"))
    )
    (net (code "98") (name "Net-(R37-Pad2)") (class "Default")
      (node (ref "R37") (pin "2") (pinfunction "2_2") (pintype "passive"))
      (node (ref "R38") (pin "1") (pinfunction "1_1") (pintype "passive"))
    )
    (net (code "99") (name "Net-(R38-Pad2)") (class "Default")
      (node (ref "R38") (pin "2") (pinfunction "2_2") (pintype "passive"))
      (node (ref "R39") (pin "1") (pinfunction "1_1") (pintype "passive"))
    )
    (net (code "100") (name "Net-(R44-Pad2)") (class "Default")
      (node (ref "R44") (pin "2") (pinfunction "2_2") (pintype "passive"))
      (node (ref "R45") (pin "1") (pinfunction "1_1") (pintype "passive"))
    )
    (net (code "101") (name "Net-(R45-Pad2)") (class "Default")
      (node (ref "R45") (pin "2") (pinfunction "2_2") (pintype "passive"))
      (node (ref "R46") (pin "1") (pinfunction "1_1") (pintype "passive"))
    )
    (net (code "102") (name "Net-(R46-Pad2)") (class "Default")
      (node (ref "R46") (pin "2") (pinfunction "2_2") (pintype "passive"))
      (node (ref "R47") (pin "1") (pinfunction "1_1") (pintype "passive"))
    )
    (net (code "103") (name "Net-(R52-Pad2)") (class "Default")
      (node (ref "R52") (pin "2") (pinfunction "2_2") (pintype "passive"))
      (node (ref "R53") (pin "1") (pinfunction "1_1") (pintype "passive"))
    )
    (net (code "104") (name "Net-(R53-Pad2)") (class "Default")
      (node (ref "R53") (pin "2") (pinfunction "2_2") (pintype "passive"))
      (node (ref "R54") (pin "1") (pinfunction "1_1") (pintype "passive"))
    )
    (net (code "105") (name "Net-(R54-Pad2)") (class "Default")
      (node (ref "R54") (pin "2") (pinfunction "2_2") (pintype "passive"))
      (node (ref "R55") (pin "1") (pinfunction "1_1") (pintype "passive"))
    )
    (net (code "106") (name "Net-(R68-Pad2)") (class "Default")
      (node (ref "R68") (pin "2") (pinfunction "2_2") (pintype "passive"))
      (node (ref "R69") (pin "1") (pinfunction "1_1") (pintype "passive"))
    )
    (net (code "107") (name "Net-(R69-Pad2)") (class "Default")
      (node (ref "R69") (pin "2") (pinfunction "2_2") (pintype "passive"))
      (node (ref "R70") (pin "1") (pinfunction "1_1") (pintype "passive"))
    )
    (net (code "108") (name "Net-(R70-Pad2)") (class "Default")
      (node (ref "R70") (pin "2") (pinfunction "2_2") (pintype "passive"))
      (node (ref "R71") (pin "1") (pinfunction "1_1") (pintype "passive"))
    )
    (net (code "109") (name "Net-(R76-Pad2)") (class "Default")
      (node (ref "R76") (pin "2") (pinfunction "2_2") (pintype "passive"))
      (node (ref "R77") (pin "1") (pinfunction "1_1") (pintype "passive"))
    )
    (net (code "110") (name "Net-(R77-Pad2)") (class "Default")
      (node (ref "R77") (pin "2") (pinfunction "2_2") (pintype "passive"))
      (node (ref "R78") (pin "1") (pinfunction "1_1") (pintype "passive"))
    )
    (net (code "111") (name "Net-(R78-Pad2)") (class "Default")
      (node (ref "R78") (pin "2") (pinfunction "2_2") (pintype "passive"))
      (node (ref "R79") (pin "1") (pinfunction "1_1") (pintype "passive"))
    )
    (net (code "112") (name "Net-(R84-Pad2)") (class "Default")
      (node (ref "R84") (pin "2") (pinfunction "2_2") (pintype "passive"))
      (node (ref "R85") (pin "1") (pinfunction "1_1") (pintype "passive"))
    )
    (net (code "113") (name "Net-(R85-Pad2)") (class "Default")
      (node (ref "R85") (pin "2") (pinfunction "2_2") (pintype "passive"))
      (node (ref "R86") (pin "1") (pinfunction "1_1") (pintype "passive"))
    )
    (net (code "114") (name "Net-(R86-Pad2)") (class "Default")
      (node (ref "R86") (pin "2") (pinfunction "2_2") (pintype "passive"))
      (node (ref "R87") (pin "1") (pinfunction "1_1") (pintype "passive"))
    )
    (net (code "115") (name "Net-(R100-Pad2)") (class "Default")
      (node (ref "R100") (pin "2") (pinfunction "2_2") (pintype "passive"))
      (node (ref "R101") (pin "1") (pinfunction "1_1") (pintype "passive"))
    )
    (net (code "116") (name "Net-(R101-Pad2)") (class "Default")
      (node (ref "R101") (pin "2") (pinfunction "2_2") (pintype "passive"))
      (node (ref "R102") (pin "1") (pinfunction "1_1") (pintype "passive"))
    )
    (net (code "117") (name "Net-(R102-Pad2)") (class "Default")
      (node (ref "R102") (pin "2") (pinfunction "2_2") (pintype "passive"))
      (node (ref "R103") (pin "1") (pinfunction "1_1") (pintype "passive"))
    )
    (net (code "118") (name "Net-(R116-Pad2)") (class "Default")
      (node (ref "R116") (pin "2") (pinfunction "2_2") (pintype "passive"))
      (node (ref "R117") (pin "1") (pinfunction "1_1") (pintype "passive"))
    )
    (net (code "119") (name "Net-(R117-Pad2)") (class "Default")
      (node (ref "R117") (pin "2") (pinfunction "2_2") (pintype "passive"))
      (node (ref "R118") (pin "1") (pinfunction "1_1") (pintype "passive"))
    )
    (net (code "120") (name "Net-(R118-Pad2)") (class "Default")
      (node (ref "R118") (pin "2") (pinfunction "2_2") (pintype "passive"))
      (node (ref "R119") (pin "1") (pinfunction "1_1") (pintype "passive"))
    )
    (net (code "121") (name "OUT_1") (class "Default")
      (node (ref "K1") (pin "4") (pinfunction "4_4") (pintype "passive"))
      (node (ref "K1") (pin "5") (pinfunction "5_5") (pintype "passive"))
      (node (ref "R25") (pin "1") (pinfunction "1_1") (pintype "passive"))
      (node (ref "R34") (pin "1") (pinfunction "1_1") (pintype "passive"))
      (node (ref "R35") (pin "1") (pinfunction "1_1") (pintype "passive"))
      (node (ref "R36") (pin "1") (pinfunction "1_1") (pintype "passive"))
    )
    (net (code "122") (name "OUT_2") (class "Default")
      (node (ref "K2") (pin "4") (pinfunction "4_4") (pintype "passive"))
      (node (ref "K2") (pin "5") (pinfunction "5_5") (pintype "passive"))
      (node (ref "R32") (pin "1") (pinfunction "1_1") (pintype "passive"))
      (node (ref "R50") (pin "1") (pinfunction "1_1") (pintype "passive"))
      (node (ref "R51") (pin "1") (pinfunction "1_1") (pintype "passive"))
      (node (ref "R52") (pin "1") (pinfunction "1_1") (pintype "passive"))
    )
    (net (code "123") (name "OUT_3") (class "Default")
      (node (ref "K3") (pin "4") (pinfunction "4_4") (pintype "passive"))
      (node (ref "K3") (pin "5") (pinfunction "5_5") (pintype "passive"))
      (node (ref "R31") (pin "1") (pinfunction "1_1") (pintype "passive"))
      (node (ref "R66") (pin "1") (pinfunction "1_1") (pintype "passive"))
      (node (ref "R67") (pin "1") (pinfunction "1_1") (pintype "passive"))
      (node (ref "R68") (pin "1") (pinfunction "1_1") (pintype "passive"))
    )
    (net (code "124") (name "OUT_4") (class "Default")
      (node (ref "K4") (pin "4") (pinfunction "4_4") (pintype "passive"))
      (node (ref "K4") (pin "5") (pinfunction "5_5") (pintype "passive"))
      (node (ref "R30") (pin "1") (pinfunction "1_1") (pintype "passive"))
      (node (ref "R82") (pin "1") (pinfunction "1_1") (pintype "passive"))
      (node (ref "R83") (pin "1") (pinfunction "1_1") (pintype "passive"))
      (node (ref "R84") (pin "1") (pinfunction "1_1") (pintype "passive"))
    )
    (net (code "125") (name "OUT_5") (class "Default")
      (node (ref "K5") (pin "4") (pinfunction "4_4") (pintype "passive"))
      (node (ref "K5") (pin "5") (pinfunction "5_5") (pintype "passive"))
      (node (ref "R26") (pin "1") (pinfunction "1_1") (pintype "passive"))
      (node (ref "R42") (pin "1") (pinfunction "1_1") (pintype "passive"))
      (node (ref "R43") (pin "1") (pinfunction "1_1") (pintype "passive"))
      (node (ref "R44") (pin "1") (pinfunction "1_1") (pintype "passive"))
    )
    (net (code "126") (name "OUT_6") (class "Default")
      (node (ref "K6") (pin "4") (pinfunction "4_4") (pintype "passive"))
      (node (ref "K6") (pin "5") (pinfunction "5_5") (pintype "passive"))
      (node (ref "R27") (pin "1") (pinfunction "1_1") (pintype "passive"))
      (node (ref "R74") (pin "1") (pinfunction "1_1") (pintype "passive"))
      (node (ref "R75") (pin "1") (pinfunction "1_1") (pintype "passive"))
      (node (ref "R76") (pin "1") (pinfunction "1_1") (pintype "passive"))
    )
    (net (code "127") (name "OUT_7") (class "Default")
      (node (ref "K7") (pin "4") (pinfunction "4_4") (pintype "passive"))
      (node (ref "K7") (pin "5") (pinfunction "5_5") (pintype "passive"))
      (node (ref "R100") (pin "1") (pinfunction "1_1") (pintype "passive"))
      (node (ref "R28") (pin "1") (pinfunction "1_1") (pintype "passive"))
      (node (ref "R98") (pin "1") (pinfunction "1_1") (pintype "passive"))
      (node (ref "R99") (pin "1") (pinfunction "1_1") (pintype "passive"))
    )
    (net (code "128") (name "OUT_8") (class "Default")
      (node (ref "K8") (pin "4") (pinfunction "4_4") (pintype "passive"))
      (node (ref "K8") (pin "5") (pinfunction "5_5") (pintype "passive"))
      (node (ref "R114") (pin "1") (pinfunction "1_1") (pintype "passive"))
      (node (ref "R115") (pin "1") (pinfunction "1_1") (pintype "passive"))
      (node (ref "R116") (pin "1") (pinfunction "1_1") (pintype "passive"))
      (node (ref "R29") (pin "1") (pinfunction "1_1") (pintype "passive"))
    )
    (net (code "129") (name "RELAY_1") (class "Default")
      (node (ref "D1") (pin "A") (pinfunction "A_A") (pintype "passive"))
      (node (ref "K1") (pin "1") (pinfunction "1_1") (pintype "passive"))
      (node (ref "R24") (pin "2") (pinfunction "2_2") (pintype "passive"))
    )
    (net (code "130") (name "RELAY_2") (class "Default")
      (node (ref "D2") (pin "A") (pinfunction "A_A") (pintype "passive"))
      (node (ref "K2") (pin "1") (pinfunction "1_1") (pintype "passive"))
      (node (ref "R23") (pin "2") (pinfunction "2_2") (pintype "passive"))
    )
    (net (code "131") (name "RELAY_3") (class "Default")
      (node (ref "D3") (pin "A") (pinfunction "A_A") (pintype "passive"))
      (node (ref "K3") (pin "1") (pinfunction "1_1") (pintype "passive"))
      (node (ref "R22") (pin "2") (pinfunction "2_2") (pintype "passive"))
    )
    (net (code "132") (name "RELAY_4") (class "Default")
      (node (ref "D4") (pin "A") (pinfunction "A_A") (pintype "passive"))
      (node (ref "K4") (pin "1") (pinfunction "1_1") (pintype "passive"))
      (node (ref "R21") (pin "2") (pinfunction "2_2") (pintype "passive"))
    )
    (net (code "133") (name "RELAY_5") (class "Default")
      (node (ref "D5") (pin "A") (pinfunction "A_A") (pintype "passive"))
      (node (ref "K5") (pin "1") (pinfunction "1_1") (pintype "passive"))
      (node (ref "R20") (pin "2") (pinfunction "2_2") (pintype "passive"))
    )
    (net (code "134") (name "RELAY_6") (class "Default")
      (node (ref "D6") (pin "A") (pinfunction "A_A") (pintype "passive"))
      (node (ref "K6") (pin "1") (pinfunction "1_1") (pintype "passive"))
      (node (ref "R19") (pin "2") (pinfunction "2_2") (pintype "passive"))
    )
    (net (code "135") (name "RELAY_7") (class "Default")
      (node (ref "D7") (pin "A") (pinfunction "A_A") (pintype "passive"))
      (node (ref "K7") (pin "1") (pinfunction "1_1") (pintype "passive"))
      (node (ref "R18") (pin "2") (pinfunction "2_2") (pintype "passive"))
    )
    (net (code "136") (name "RELAY_8") (class "Default")
      (node (ref "D8") (pin "A") (pinfunction "A_A") (pintype "passive"))
      (node (ref "K8") (pin "1") (pinfunction "1_1") (pintype "passive"))
      (node (ref "R17") (pin "2") (pinfunction "2_2") (pintype "passive"))
    )
    (net (code "137") (name "REL_0") (class "Default")
      (node (ref "IC3") (pin "8") (pinfunction "8B_8") (pintype "bidirectional"))
      (node (ref "IC4") (pin "17") (pinfunction "IO1.0_17") (pintype "bidirectional"))
    )
    (net (code "138") (name "REL_1") (class "Default")
      (node (ref "IC3") (pin "7") (pinfunction "7B_7") (pintype "bidirectional"))
      (node (ref "IC4") (pin "18") (pinfunction "IO1.1_18") (pintype "bidirectional"))
    )
    (net (code "139") (name "REL_2") (class "Default")
      (node (ref "IC3") (pin "6") (pinfunction "6B_6") (pintype "bidirectional"))
      (node (ref "IC4") (pin "19") (pinfunction "IO1.2_19") (pintype "bidirectional"))
    )
    (net (code "140") (name "REL_3") (class "Default")
      (node (ref "IC3") (pin "5") (pinfunction "5B_5") (pintype "bidirectional"))
      (node (ref "IC4") (pin "20") (pinfunction "IO1.3_20") (pintype "bidirectional"))
    )
    (net (code "141") (name "REL_4") (class "Default")
      (node (ref "IC3") (pin "4") (pinfunction "4B_4") (pintype "bidirectional"))
      (node (ref "IC4") (pin "21") (pinfunction "IO1.4_21") (pintype "bidirectional"))
    )
    (net (code "142") (name "REL_5") (class "Default")
      (node (ref "IC3") (pin "3") (pinfunction "3B_3") (pintype "bidirectional"))
      (node (ref "IC4") (pin "22") (pinfunction "IO1.5_22") (pintype "bidirectional"))
    )
    (net (code "143") (name "REL_6") (class "Default")
      (node (ref "IC3") (pin "2") (pinfunction "2B_2") (pintype "bidirectional"))
      (node (ref "IC4") (pin "23") (pinfunction "IO1.6_23") (pintype "bidirectional"))
    )
    (net (code "144") (name "REL_7") (class "Default")
      (node (ref "IC3") (pin "1") (pinfunction "1B_1") (pintype "bidirectional"))
      (node (ref "IC4") (pin "24") (pinfunction "IO1.7_24") (pintype "bidirectional"))
    )
    (net (code "145") (name "RX_CH1") (class "Default")
      (node (ref "IC6") (pin "8") (pinfunction "RX_8") (pintype "bidirectional"))
    )
    (net (code "146") (name "RX_CH2") (class "Default")
      (node (ref "IC8") (pin "8") (pinfunction "RX_8") (pintype "bidirectional"))
    )
    (net (code "147") (name "RX_CH3") (class "Default")
      (node (ref "IC10") (pin "8") (pinfunction "RX_8") (pintype "bidirectional"))
    )
    (net (code "148") (name "RX_CH4") (class "Default")
      (node (ref "IC12") (pin "8") (pinfunction "RX_8") (pintype "bidirectional"))
    )
    (net (code "149") (name "RX_CH5") (class "Default")
      (node (ref "IC7") (pin "8") (pinfunction "RX_8") (pintype "bidirectional"))
    )
    (net (code "150") (name "RX_CH6") (class "Default")
      (node (ref "IC11") (pin "8") (pinfunction "RX_8") (pintype "bidirectional"))
    )
    (net (code "151") (name "RX_CH7") (class "Default")
      (node (ref "IC14") (pin "8") (pinfunction "RX_8") (pintype "bidirectional"))
    )
    (net (code "152") (name "RX_CH8") (class "Default")
      (node (ref "IC16") (pin "8") (pinfunction "RX_8") (pintype "bidirectional"))
    )
    (net (code "153") (name "TX_CH1") (class "Default")
      (node (ref "IC6") (pin "6") (pinfunction "TX_6") (pintype "bidirectional"))
      (node (ref "OPT1") (pin "8") (pinfunction "8_8") (pintype "passive"))
    )
    (net (code "154") (name "TX_CH2") (class "Default")
      (node (ref "IC8") (pin "6") (pinfunction "TX_6") (pintype "bidirectional"))
      (node (ref "OPT1") (pin "6") (pinfunction "6_6") (pintype "passive"))
    )
    (net (code "155") (name "TX_CH3") (class "Default")
      (node (ref "IC10") (pin "6") (pinfunction "TX_6") (pintype "bidirectional"))
      (node (ref "OPT1") (pin "4") (pinfunction "4_4") (pintype "passive"))
    )
    (net (code "156") (name "TX_CH4") (class "Default")
      (node (ref "IC12") (pin "6") (pinfunction "TX_6") (pintype "bidirectional"))
      (node (ref "OPT1") (pin "2") (pinfunction "2_2") (pintype "passive"))
    )
    (net (code "157") (name "TX_CH5") (class "Default")
      (node (ref "IC7") (pin "6") (pinfunction "TX_6") (pintype "bidirectional"))
      (node (ref "OPT3") (pin "2") (pinfunction "2_2") (pintype "passive"))
    )
    (net (code "158") (name "TX_CH6") (class "Default")
      (node (ref "IC11") (pin "6") (pinfunction "TX_6") (pintype "bidirectional"))
      (node (ref "OPT3") (pin "4") (pinfunction "4_4") (pintype "passive"))
    )
    (net (code "159") (name "TX_CH7") (class "Default")
      (node (ref "IC14") (pin "6") (pinfunction "TX_6") (pintype "bidirectional"))
      (node (ref "OPT2") (pin "2") (pinfunction "2_2") (pintype "passive"))
    )
    (net (code "160") (name "TX_CH8") (class "Default")
      (node (ref "IC16") (pin "6") (pinfunction "TX_6") (pintype "bidirectional"))
      (node (ref "OPT2") (pin "4") (pinfunction "4_4") (pintype "passive"))
    )
    (net (code "161") (name "TX_MUX1") (class "Default")
      (node (ref "IC9") (pin "4") (pinfunction "D0_4") (pintype "bidirectional"))
      (node (ref "OPT1") (pin "10") (pinfunction "10_10") (pintype "passive"))
      (node (ref "R89") (pin "4") (pinfunction "4_4") (pintype "passive"))
    )
    (net (code "162") (name "TX_MUX2") (class "Default")
      (node (ref "IC9") (pin "3") (pinfunction "D1_3") (pintype "bidirectional"))
      (node (ref "OPT1") (pin "12") (pinfunction "12_12") (pintype "passive"))
      (node (ref "R89") (pin "3") (pinfunction "3_3") (pintype "passive"))
    )
    (net (code "163") (name "TX_MUX3") (class "Default")
      (node (ref "IC9") (pin "2") (pinfunction "D2_2") (pintype "bidirectional"))
      (node (ref "OPT1") (pin "14") (pinfunction "14_14") (pintype "passive"))
      (node (ref "R89") (pin "2") (pinfunction "2_2") (pintype "passive"))
    )
    (net (code "164") (name "TX_MUX4") (class "Default")
      (node (ref "IC9") (pin "1") (pinfunction "D3_1") (pintype "bidirectional"))
      (node (ref "OPT1") (pin "16") (pinfunction "16_16") (pintype "passive"))
      (node (ref "R89") (pin "1") (pinfunction "1_1") (pintype "passive"))
    )
    (net (code "165") (name "TX_MUX5") (class "Default")
      (node (ref "IC9") (pin "15") (pinfunction "D4_15") (pintype "bidirectional"))
      (node (ref "OPT3") (pin "8") (pinfunction "8_8") (pintype "passive"))
      (node (ref "R90") (pin "1") (pinfunction "1_1") (pintype "passive"))
    )
    (net (code "166") (name "TX_MUX6") (class "Default")
      (node (ref "IC9") (pin "14") (pinfunction "D5_14") (pintype "bidirectional"))
      (node (ref "OPT3") (pin "6") (pinfunction "6_6") (pintype "passive"))
      (node (ref "R90") (pin "2") (pinfunction "2_2") (pintype "passive"))
    )
    (net (code "167") (name "TX_MUX7") (class "Default")
      (node (ref "IC9") (pin "13") (pinfunction "D6_13") (pintype "bidirectional"))
      (node (ref "OPT2") (pin "8") (pinfunction "8_8") (pintype "passive"))
      (node (ref "R90") (pin "3") (pinfunction "3_3") (pintype "passive"))
    )
    (net (code "168") (name "TX_MUX8") (class "Default")
      (node (ref "IC9") (pin "12") (pinfunction "D7_12") (pintype "bidirectional"))
      (node (ref "OPT2") (pin "6") (pinfunction "6_6") (pintype "passive"))
      (node (ref "R90") (pin "4") (pinfunction "4_4") (pintype "passive"))
    )
    (net (code "169") (name "UART0_RX") (class "Default")
      (node (ref "J1") (pin "10") (pinfunction "10_10") (pintype "bidirectional"))
    )
    (net (code "170") (name "UART0_TX") (class "Default")
      (node (ref "J1") (pin "11") (pinfunction "11_11") (pintype "bidirectional"))
      (node (ref "R91") (pin "2") (pinfunction "2_2") (pintype "passive"))
      (node (ref "R92") (pin "2") (pinfunction "2_2") (pintype "passive"))
    )
    (net (code "171") (name "unconnected-(IC4-INTA-Pad16)") (class "Default")
      (node (ref "IC4") (pin "16") (pinfunction "INTA_16") (pintype "bidirectional"))
    )
    (net (code "172") (name "unconnected-(IC4-INTB-Pad15)") (class "Default")
      (node (ref "IC4") (pin "15") (pinfunction "INTB_15") (pintype "bidirectional"))
    )
    (net (code "173") (name "unconnected-(IC4-IO2.4-Pad1)") (class "Default")
      (node (ref "IC4") (pin "1") (pinfunction "IO2.4_1") (pintype "bidirectional"))
    )
    (net (code "174") (name "unconnected-(IC4-IO2.5-Pad2)") (class "Default")
      (node (ref "IC4") (pin "2") (pinfunction "IO2.5_2") (pintype "bidirectional"))
    )
    (net (code "175") (name "unconnected-(IC4-IO2.6-Pad3)") (class "Default")
      (node (ref "IC4") (pin "3") (pinfunction "IO2.6_3") (pintype "bidirectional"))
    )
    (net (code "176") (name "unconnected-(IC4-IO2.7-Pad4)") (class "Default")
      (node (ref "IC4") (pin "4") (pinfunction "IO2.7_4") (pintype "bidirectional"))
    )
    (net (code "177") (name "unconnected-(IC6-PF-Pad7)") (class "Default")
      (node (ref "IC6") (pin "7") (pinfunction "PF_7") (pintype "bidirectional"))
    )
    (net (code "178") (name "unconnected-(IC7-PF-Pad7)") (class "Default")
      (node (ref "IC7") (pin "7") (pinfunction "PF_7") (pintype "bidirectional"))
    )
    (net (code "179") (name "unconnected-(IC8-PF-Pad7)") (class "Default")
      (node (ref "IC8") (pin "7") (pinfunction "PF_7") (pintype "bidirectional"))
    )
    (net (code "180") (name "unconnected-(IC10-PF-Pad7)") (class "Default")
      (node (ref "IC10") (pin "7") (pinfunction "PF_7") (pintype "bidirectional"))
    )
    (net (code "181") (name "unconnected-(IC11-PF-Pad7)") (class "Default")
      (node (ref "IC11") (pin "7") (pinfunction "PF_7") (pintype "bidirectional"))
    )
    (net (code "182") (name "unconnected-(IC12-PF-Pad7)") (class "Default")
      (node (ref "IC12") (pin "7") (pinfunction "PF_7") (pintype "bidirectional"))
    )
    (net (code "183") (name "unconnected-(IC14-PF-Pad7)") (class "Default")
      (node (ref "IC14") (pin "7") (pinfunction "PF_7") (pintype "bidirectional"))
    )
    (net (code "184") (name "unconnected-(IC16-PF-Pad7)") (class "Default")
      (node (ref "IC16") (pin "7") (pinfunction "PF_7") (pintype "bidirectional"))
    )
    (net (code "185") (name "unconnected-(J1-Pad17)") (class "Default")
      (node (ref "J1") (pin "17") (pinfunction "17_17") (pintype "bidirectional"))
    )
    (net (code "186") (name "unconnected-(J1-Pad18)") (class "Default")
      (node (ref "J1") (pin "18") (pinfunction "18_18") (pintype "bidirectional"))
    )
    (net (code "187") (name "unconnected-(J1-Pad19)") (class "Default")
      (node (ref "J1") (pin "19") (pinfunction "19_19") (pintype "bidirectional"))
    )
    (net (code "188") (name "unconnected-(J1-Pad20)") (class "Default")
      (node (ref "J1") (pin "20") (pinfunction "20_20") (pintype "bidirectional"))
    )
    (net (code "189") (name "unconnected-(R64-Pad5)") (class "Default")
      (node (ref "R64") (pin "5") (pinfunction "5_5") (pintype "passive"))
    )
    (net (code "190") (name "unconnected-(R64-Pad6)") (class "Default")
      (node (ref "R64") (pin "6") (pinfunction "6_6") (pintype "passive"))
    )
    (net (code "191") (name "unconnected-(R110-Pad5)") (class "Default")
      (node (ref "R110") (pin "5") (pinfunction "5_5") (pintype "passive"))
    )
    (net (code "192") (name "unconnected-(R110-Pad6)") (class "Default")
      (node (ref "R110") (pin "6") (pinfunction "6_6") (pintype "passive"))
    )
  )
)
